# BB-cape.net
KiCad netlist of a schematic drawn in EAGLE
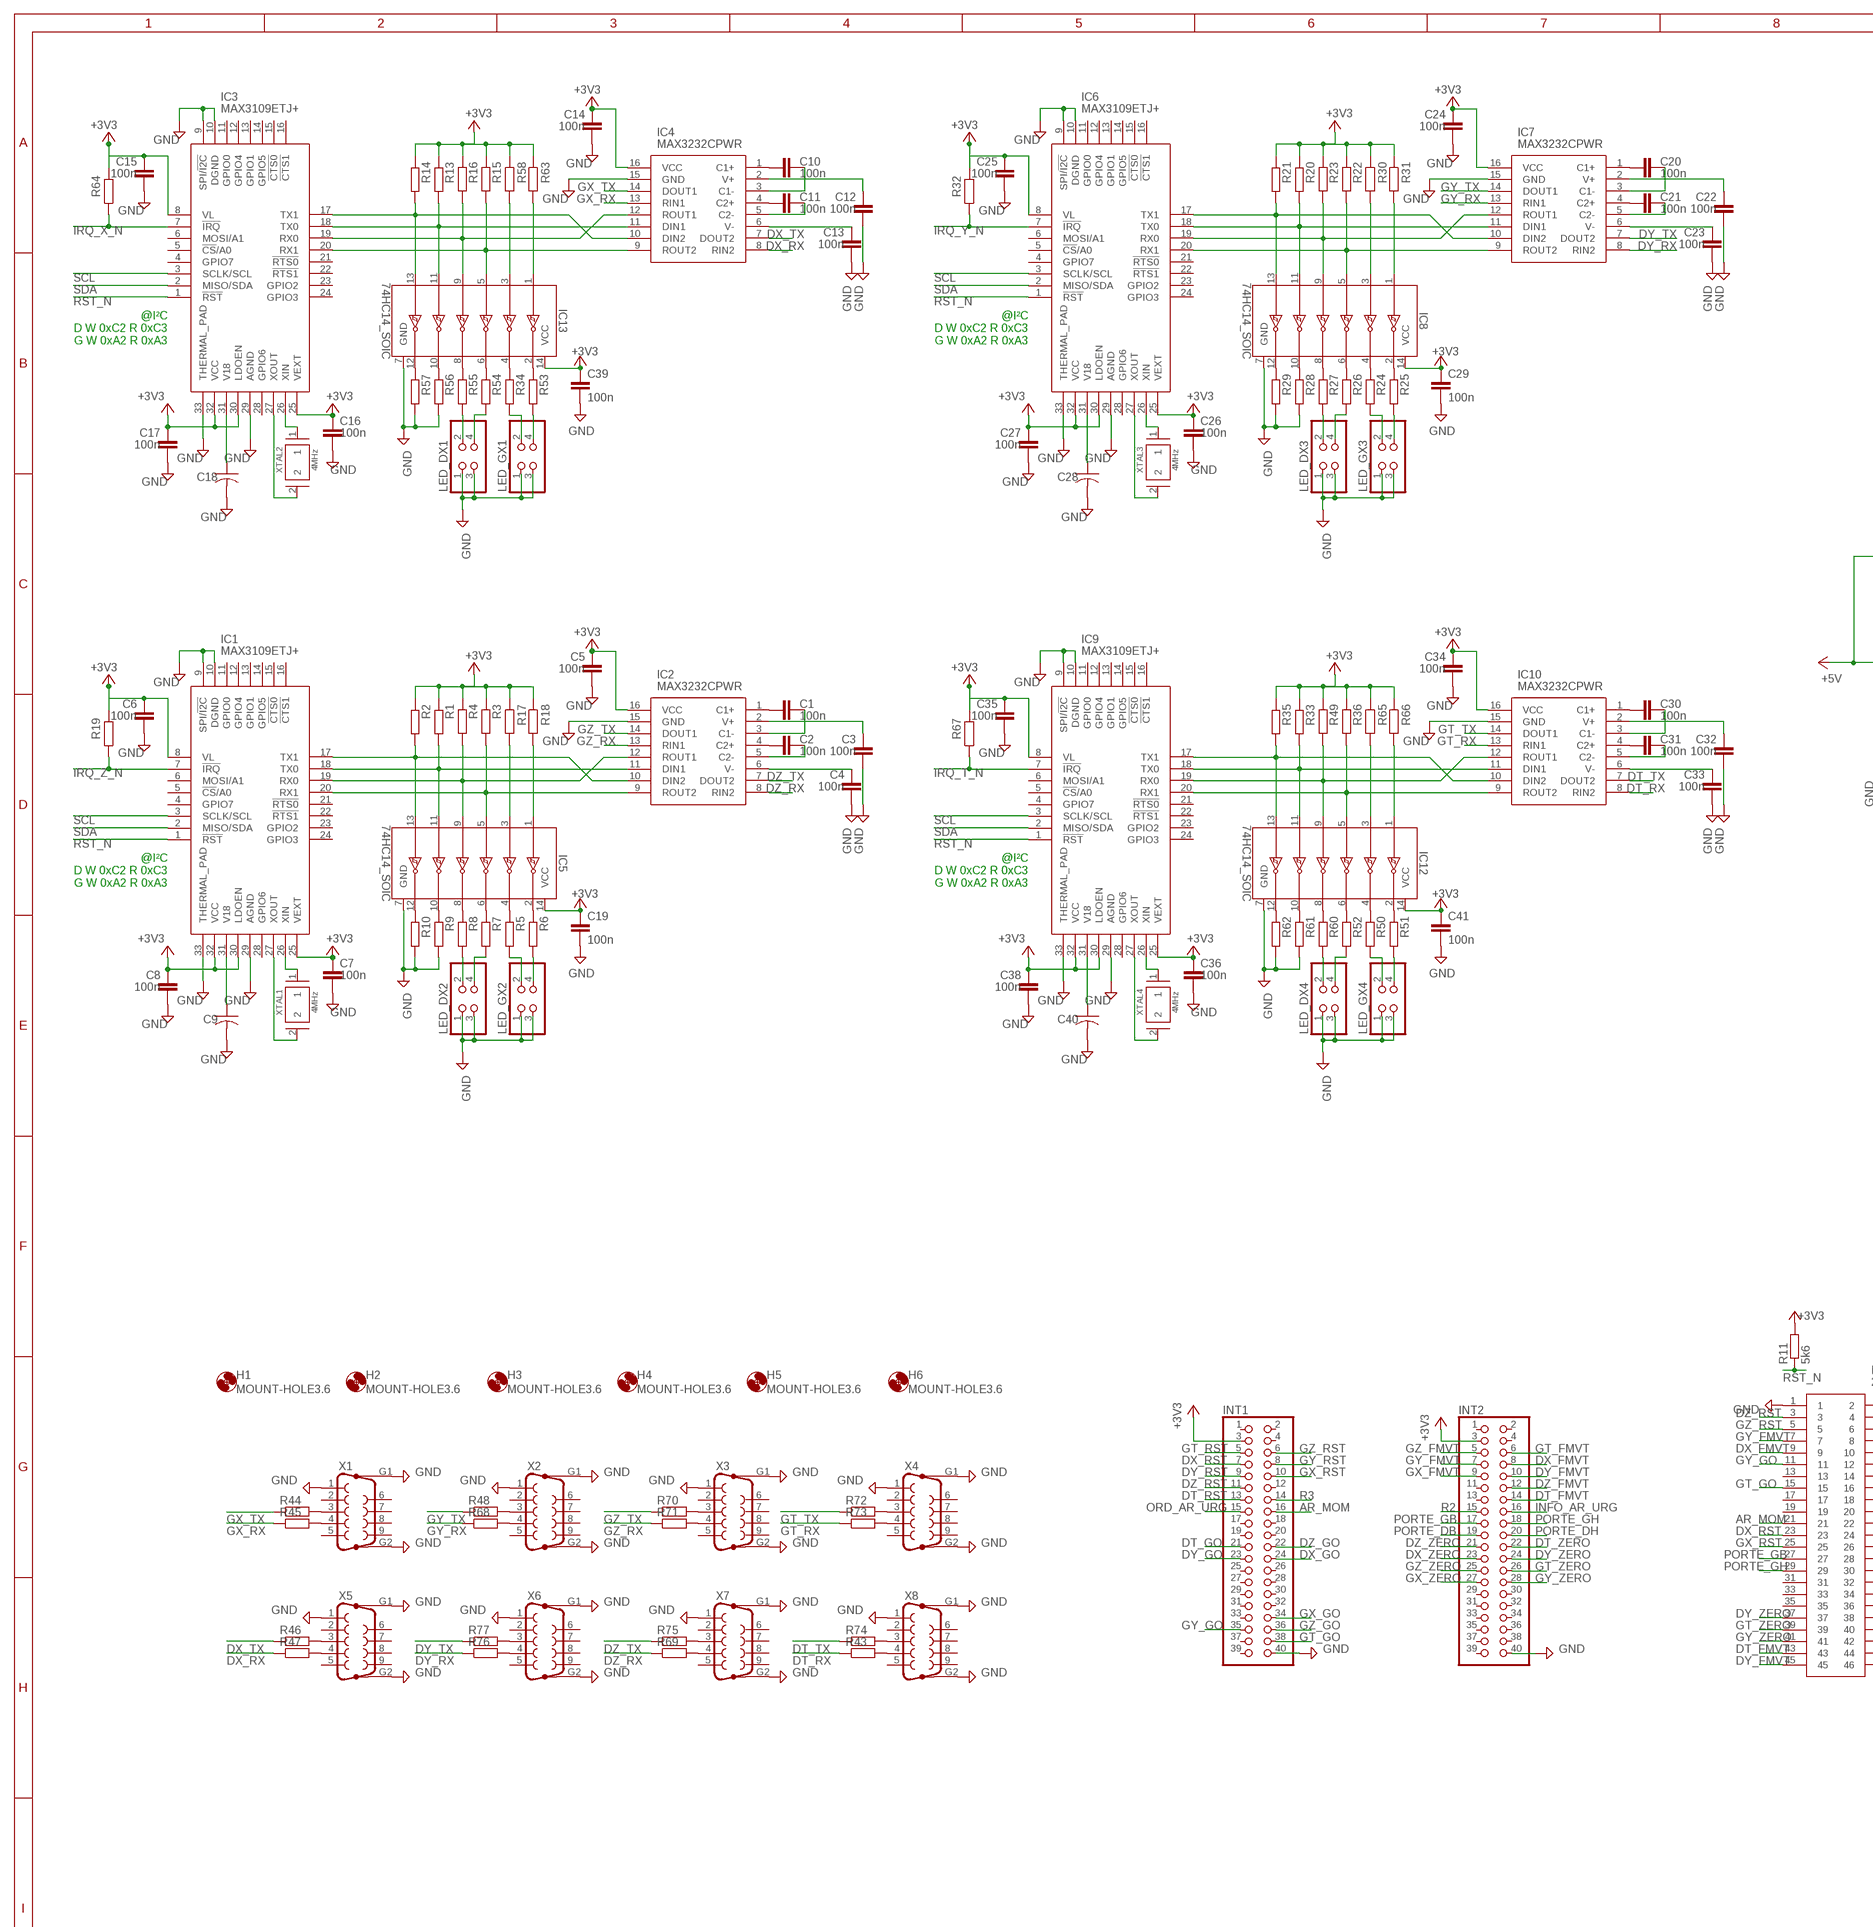
[diagram p0: schematic, sheet 1, part 1 of 2]
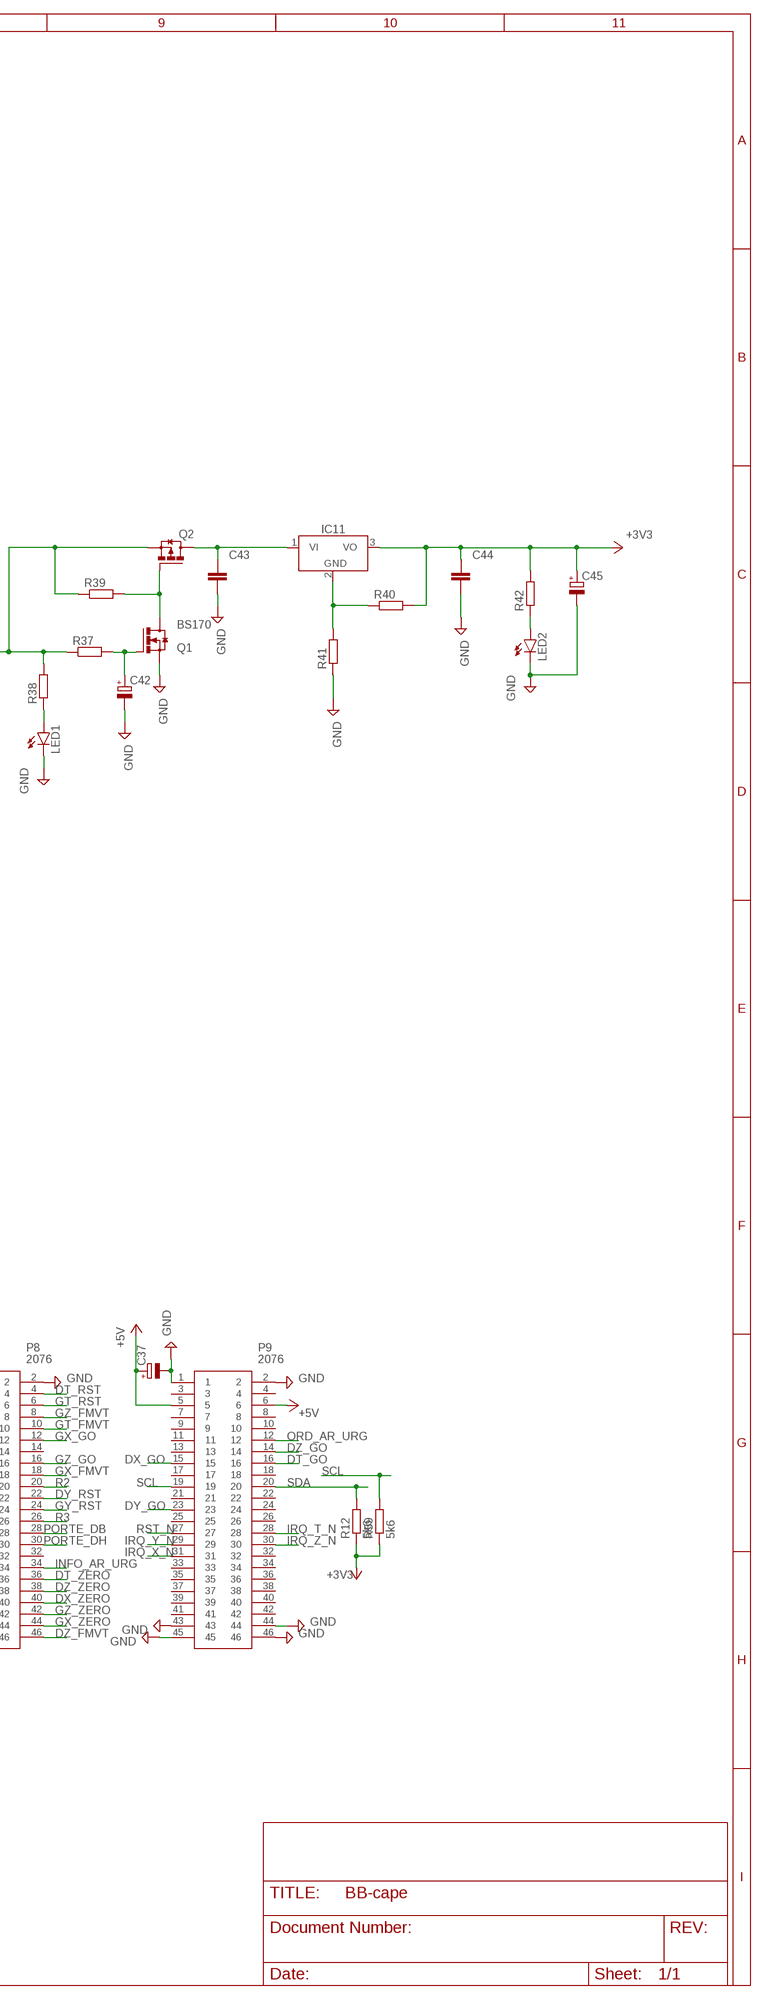
[diagram p1: schematic, sheet 1, part 2 of 2]

(export (version "E")
  (design (tool "Eeschema 10.0.6"))
  (components
    (comp (ref "C1")
      (value "100n")
      (footprint "eagle-import:C0603")
      (libsource (lib "eagle-import") (part "C-EUC0603"))
    )
    (comp (ref "C2")
      (value "100n")
      (footprint "eagle-import:C0603")
      (libsource (lib "eagle-import") (part "C-EUC0603"))
    )
    (comp (ref "C3")
      (value "100n")
      (footprint "eagle-import:C0603")
      (libsource (lib "eagle-import") (part "C-EUC0603"))
    )
    (comp (ref "C4")
      (value "100n")
      (footprint "eagle-import:C0603")
      (libsource (lib "eagle-import") (part "C-EUC0603"))
    )
    (comp (ref "C5")
      (value "100n")
      (footprint "eagle-import:C0603")
      (libsource (lib "eagle-import") (part "C-EUC0603"))
    )
    (comp (ref "C6")
      (value "100n")
      (footprint "eagle-import:C0603")
      (libsource (lib "eagle-import") (part "C-EUC0603"))
    )
    (comp (ref "C7")
      (value "100n")
      (footprint "eagle-import:C0603")
      (libsource (lib "eagle-import") (part "C-EUC0603"))
    )
    (comp (ref "C8")
      (value "100n")
      (footprint "eagle-import:C0603")
      (libsource (lib "eagle-import") (part "C-EUC0603"))
    )
    (comp (ref "C9")
      (value "C-USC1206")
      (footprint "eagle-import:C1206")
      (libsource (lib "eagle-import") (part "C-USC1206"))
    )
    (comp (ref "C10")
      (value "100n")
      (footprint "eagle-import:C0603")
      (libsource (lib "eagle-import") (part "C-EUC0603"))
    )
    (comp (ref "C11")
      (value "100n")
      (footprint "eagle-import:C0603")
      (libsource (lib "eagle-import") (part "C-EUC0603"))
    )
    (comp (ref "C12")
      (value "100n")
      (footprint "eagle-import:C0603")
      (libsource (lib "eagle-import") (part "C-EUC0603"))
    )
    (comp (ref "C13")
      (value "100n")
      (footprint "eagle-import:C0603")
      (libsource (lib "eagle-import") (part "C-EUC0603"))
    )
    (comp (ref "C14")
      (value "100n")
      (footprint "eagle-import:C0603")
      (libsource (lib "eagle-import") (part "C-EUC0603"))
    )
    (comp (ref "C15")
      (value "100n")
      (footprint "eagle-import:C0603")
      (libsource (lib "eagle-import") (part "C-EUC0603"))
    )
    (comp (ref "C16")
      (value "100n")
      (footprint "eagle-import:C0603")
      (libsource (lib "eagle-import") (part "C-EUC0603"))
    )
    (comp (ref "C17")
      (value "100n")
      (footprint "eagle-import:C0603")
      (libsource (lib "eagle-import") (part "C-EUC0603"))
    )
    (comp (ref "C18")
      (value "C-USC1206")
      (footprint "eagle-import:C1206")
      (libsource (lib "eagle-import") (part "C-USC1206"))
    )
    (comp (ref "C19")
      (value "100n")
      (footprint "eagle-import:C0603")
      (libsource (lib "eagle-import") (part "C-EUC0603"))
    )
    (comp (ref "C20")
      (value "100n")
      (footprint "eagle-import:C0603")
      (libsource (lib "eagle-import") (part "C-EUC0603"))
    )
    (comp (ref "C21")
      (value "100n")
      (footprint "eagle-import:C0603")
      (libsource (lib "eagle-import") (part "C-EUC0603"))
    )
    (comp (ref "C22")
      (value "100n")
      (footprint "eagle-import:C0603")
      (libsource (lib "eagle-import") (part "C-EUC0603"))
    )
    (comp (ref "C23")
      (value "100n")
      (footprint "eagle-import:C0603")
      (libsource (lib "eagle-import") (part "C-EUC0603"))
    )
    (comp (ref "C24")
      (value "100n")
      (footprint "eagle-import:C0603")
      (libsource (lib "eagle-import") (part "C-EUC0603"))
    )
    (comp (ref "C25")
      (value "100n")
      (footprint "eagle-import:C0603")
      (libsource (lib "eagle-import") (part "C-EUC0603"))
    )
    (comp (ref "C26")
      (value "100n")
      (footprint "eagle-import:C0603")
      (libsource (lib "eagle-import") (part "C-EUC0603"))
    )
    (comp (ref "C27")
      (value "100n")
      (footprint "eagle-import:C0603")
      (libsource (lib "eagle-import") (part "C-EUC0603"))
    )
    (comp (ref "C28")
      (value "C-USC1206")
      (footprint "eagle-import:C1206")
      (libsource (lib "eagle-import") (part "C-USC1206"))
    )
    (comp (ref "C29")
      (value "100n")
      (footprint "eagle-import:C0603")
      (libsource (lib "eagle-import") (part "C-EUC0603"))
    )
    (comp (ref "C30")
      (value "100n")
      (footprint "eagle-import:C0603")
      (libsource (lib "eagle-import") (part "C-EUC0603"))
    )
    (comp (ref "C31")
      (value "100n")
      (footprint "eagle-import:C0603")
      (libsource (lib "eagle-import") (part "C-EUC0603"))
    )
    (comp (ref "C32")
      (value "100n")
      (footprint "eagle-import:C0603")
      (libsource (lib "eagle-import") (part "C-EUC0603"))
    )
    (comp (ref "C33")
      (value "100n")
      (footprint "eagle-import:C0603")
      (libsource (lib "eagle-import") (part "C-EUC0603"))
    )
    (comp (ref "C34")
      (value "100n")
      (footprint "eagle-import:C0603")
      (libsource (lib "eagle-import") (part "C-EUC0603"))
    )
    (comp (ref "C35")
      (value "100n")
      (footprint "eagle-import:C0603")
      (libsource (lib "eagle-import") (part "C-EUC0603"))
    )
    (comp (ref "C36")
      (value "100n")
      (footprint "eagle-import:C0603")
      (libsource (lib "eagle-import") (part "C-EUC0603"))
    )
    (comp (ref "C37")
      (value "CPOL-EUE2.5-6")
      (footprint "eagle-import:E2,5-6")
      (libsource (lib "eagle-import") (part "CPOL-EUE2.5-6"))
    )
    (comp (ref "C38")
      (value "100n")
      (footprint "eagle-import:C0603")
      (libsource (lib "eagle-import") (part "C-EUC0603"))
    )
    (comp (ref "C39")
      (value "100n")
      (footprint "eagle-import:C0603")
      (libsource (lib "eagle-import") (part "C-EUC0603"))
    )
    (comp (ref "C40")
      (value "C-USC1206")
      (footprint "eagle-import:C1206")
      (libsource (lib "eagle-import") (part "C-USC1206"))
    )
    (comp (ref "C41")
      (value "100n")
      (footprint "eagle-import:C0603")
      (libsource (lib "eagle-import") (part "C-EUC0603"))
    )
    (comp (ref "C42")
      (value "CPOL-EUE2.5-6")
      (footprint "eagle-import:E2,5-6")
      (libsource (lib "eagle-import") (part "CPOL-EUE2.5-6"))
    )
    (comp (ref "C43")
      (value "C_CHIP-1210(3225-METRIC)")
      (footprint "eagle-import:CAPC3225X135")
      (libsource (lib "eagle-import") (part "CCHIP-1210(3225-METRIC)_"))
    )
    (comp (ref "C44")
      (value "C_CHIP-1210(3225-METRIC)")
      (footprint "eagle-import:CAPC3225X135")
      (libsource (lib "eagle-import") (part "CCHIP-1210(3225-METRIC)_"))
    )
    (comp (ref "C45")
      (value "CPOL-EUE2.5-6")
      (footprint "eagle-import:E2,5-6")
      (libsource (lib "eagle-import") (part "CPOL-EUE2.5-6"))
    )
    (comp (ref "H1")
      (value "MOUNT-HOLE3.6")
      (footprint "eagle-import:3,6")
      (libsource (lib "eagle-import") (part "MOUNT-HOLE3.6"))
    )
    (comp (ref "H2")
      (value "MOUNT-HOLE3.6")
      (footprint "eagle-import:3,6")
      (libsource (lib "eagle-import") (part "MOUNT-HOLE3.6"))
    )
    (comp (ref "H3")
      (value "MOUNT-HOLE3.6")
      (footprint "eagle-import:3,6")
      (libsource (lib "eagle-import") (part "MOUNT-HOLE3.6"))
    )
    (comp (ref "H4")
      (value "MOUNT-HOLE3.6")
      (footprint "eagle-import:3,6")
      (libsource (lib "eagle-import") (part "MOUNT-HOLE3.6"))
    )
    (comp (ref "H5")
      (value "MOUNT-HOLE3.6")
      (footprint "eagle-import:3,6")
      (libsource (lib "eagle-import") (part "MOUNT-HOLE3.6"))
    )
    (comp (ref "H6")
      (value "MOUNT-HOLE3.6")
      (footprint "eagle-import:3,6")
      (libsource (lib "eagle-import") (part "MOUNT-HOLE3.6"))
    )
    (comp (ref "IC1")
      (value "MAX3109ETJ+")
      (footprint "eagle-import:QFN50P500X500X80-33N")
      (fields (field (name "MOUSER_PART_NUMBER") "700-MAX3109ETJ+"))
      (libsource (lib "eagle-import") (part "MAX3109ETJ+"))
    )
    (comp (ref "IC2")
      (value "MAX3232CPWR")
      (footprint "eagle-import:SOP65P640X120-16N")
      (fields (field (name "MOUSER_PART_NUMBER") "595-MAX3232CPWR"))
      (libsource (lib "eagle-import") (part "MAX3232CPWR"))
    )
    (comp (ref "IC3")
      (value "MAX3109ETJ+")
      (footprint "eagle-import:QFN50P500X500X80-33N")
      (fields (field (name "MOUSER_PART_NUMBER") "700-MAX3109ETJ+"))
      (libsource (lib "eagle-import") (part "MAX3109ETJ+"))
    )
    (comp (ref "IC4")
      (value "MAX3232CPWR")
      (footprint "eagle-import:SOP65P640X120-16N")
      (fields (field (name "MOUSER_PART_NUMBER") "595-MAX3232CPWR"))
      (libsource (lib "eagle-import") (part "MAX3232CPWR"))
    )
    (comp (ref "IC5")
      (value "74HC14_SOIC")
      (footprint "eagle-import:SOIC127P600X175-14N")
      (fields (field (name "MANUFACTURER") "Generic"))
      (libsource (lib "eagle-import") (part "74HC14_SOIC"))
    )
    (comp (ref "IC6")
      (value "MAX3109ETJ+")
      (footprint "eagle-import:QFN50P500X500X80-33N")
      (fields (field (name "MOUSER_PART_NUMBER") "700-MAX3109ETJ+"))
      (libsource (lib "eagle-import") (part "MAX3109ETJ+"))
    )
    (comp (ref "IC7")
      (value "MAX3232CPWR")
      (footprint "eagle-import:SOP65P640X120-16N")
      (fields (field (name "MOUSER_PART_NUMBER") "595-MAX3232CPWR"))
      (libsource (lib "eagle-import") (part "MAX3232CPWR"))
    )
    (comp (ref "IC8")
      (value "74HC14_SOIC")
      (footprint "eagle-import:SOIC127P600X175-14N")
      (fields (field (name "MANUFACTURER") "Generic"))
      (libsource (lib "eagle-import") (part "74HC14_SOIC"))
    )
    (comp (ref "IC9")
      (value "MAX3109ETJ+")
      (footprint "eagle-import:QFN50P500X500X80-33N")
      (fields (field (name "MOUSER_PART_NUMBER") "700-MAX3109ETJ+"))
      (libsource (lib "eagle-import") (part "MAX3109ETJ+"))
    )
    (comp (ref "IC10")
      (value "MAX3232CPWR")
      (footprint "eagle-import:SOP65P640X120-16N")
      (fields (field (name "MOUSER_PART_NUMBER") "595-MAX3232CPWR"))
      (libsource (lib "eagle-import") (part "MAX3232CPWR"))
    )
    (comp (ref "IC11")
      (value "LM7805_TO220V")
      (footprint "eagle-import:TO220V")
      (fields (field (name "MANUFACTURER") "Generic"))
      (libsource (lib "eagle-import") (part "LM7805_TO220V"))
    )
    (comp (ref "IC12")
      (value "74HC14_SOIC")
      (footprint "eagle-import:SOIC127P600X175-14N")
      (fields (field (name "MANUFACTURER") "Generic"))
      (libsource (lib "eagle-import") (part "74HC14_SOIC"))
    )
    (comp (ref "IC13")
      (value "74HC14_SOIC")
      (footprint "eagle-import:SOIC127P600X175-14N")
      (fields (field (name "MANUFACTURER") "Generic"))
      (libsource (lib "eagle-import") (part "74HC14_SOIC"))
    )
    (comp (ref "INT1")
      (value "PINHD-2X20")
      (footprint "eagle-import:2X20")
      (libsource (lib "eagle-import") (part "PINHD-2X20"))
    )
    (comp (ref "INT2")
      (value "PINHD-2X20")
      (footprint "eagle-import:2X20")
      (libsource (lib "eagle-import") (part "PINHD-2X20"))
    )
    (comp (ref "LED1")
      (value "TLLY4400")
      (footprint "eagle-import:LED3MM")
      (fields (field (name "MF") "VISHAY SEMICONDUCTOR"))
      (libsource (lib "eagle-import") (part "TLLY4400"))
    )
    (comp (ref "LED2")
      (value "TLLY4400")
      (footprint "eagle-import:LED3MM")
      (fields (field (name "MF") "VISHAY SEMICONDUCTOR"))
      (libsource (lib "eagle-import") (part "TLLY4400"))
    )
    (comp (ref "LED_DX1")
      (value "PINHD-2X2")
      (footprint "eagle-import:2X02")
      (libsource (lib "eagle-import") (part "PINHD-2X2"))
    )
    (comp (ref "LED_DX2")
      (value "PINHD-2X2")
      (footprint "eagle-import:2X02")
      (libsource (lib "eagle-import") (part "PINHD-2X2"))
    )
    (comp (ref "LED_DX3")
      (value "PINHD-2X2")
      (footprint "eagle-import:2X02")
      (libsource (lib "eagle-import") (part "PINHD-2X2"))
    )
    (comp (ref "LED_DX4")
      (value "PINHD-2X2")
      (footprint "eagle-import:2X02")
      (libsource (lib "eagle-import") (part "PINHD-2X2"))
    )
    (comp (ref "LED_GX1")
      (value "PINHD-2X2")
      (footprint "eagle-import:2X02")
      (libsource (lib "eagle-import") (part "PINHD-2X2"))
    )
    (comp (ref "LED_GX2")
      (value "PINHD-2X2")
      (footprint "eagle-import:2X02")
      (libsource (lib "eagle-import") (part "PINHD-2X2"))
    )
    (comp (ref "LED_GX3")
      (value "PINHD-2X2")
      (footprint "eagle-import:2X02")
      (libsource (lib "eagle-import") (part "PINHD-2X2"))
    )
    (comp (ref "LED_GX4")
      (value "PINHD-2X2")
      (footprint "eagle-import:2X02")
      (libsource (lib "eagle-import") (part "PINHD-2X2"))
    )
    (comp (ref "P8")
      (value "2076")
      (footprint "eagle-import:HDRV46W64P254_2X23_5842X500X87")
      (fields (field (name "MOUSER_PART_NUMBER") "485-2076"))
      (libsource (lib "eagle-import") (part "2076"))
    )
    (comp (ref "P9")
      (value "2076")
      (footprint "eagle-import:HDRV46W64P254_2X23_5842X500X87")
      (fields (field (name "MOUSER_PART_NUMBER") "485-2076"))
      (libsource (lib "eagle-import") (part "2076"))
    )
    (comp (ref "Q1")
      (value "BS170")
      (footprint "eagle-import:TO92-3")
      (fields
        (field (name "DIGIKEY_PART_NUMBER") "2156-BS170-ND")
        (field (name "MANUFACTURER") "Fairchild Semiconductor")
        (field (name "CREATED_BY") "PCBLayout.com")
      )
      (libsource (lib "eagle-import") (part "BS170"))
    )
    (comp (ref "Q2")
      (value "IRF9540PBF")
      (footprint "eagle-import:TO-220")
      (fields
        (field (name "DIGIKEY_PART_NUMBER") "IRF9540PBF-ND")
        (field (name "MANUFACTURER") "Vishay Siliconix")
        (field (name "CREATED_BY") "PCBLayout.com")
      )
      (libsource (lib "eagle-import") (part "IRF9540PBF"))
    )
    (comp (ref "R1")
      (value "R-EU_R0603")
      (footprint "eagle-import:R0603")
      (libsource (lib "eagle-import") (part "R-EU_R0603"))
    )
    (comp (ref "R2")
      (value "R-EU_R0603")
      (footprint "eagle-import:R0603")
      (libsource (lib "eagle-import") (part "R-EU_R0603"))
    )
    (comp (ref "R3")
      (value "R-EU_R0603")
      (footprint "eagle-import:R0603")
      (libsource (lib "eagle-import") (part "R-EU_R0603"))
    )
    (comp (ref "R4")
      (value "R-EU_R0603")
      (footprint "eagle-import:R0603")
      (libsource (lib "eagle-import") (part "R-EU_R0603"))
    )
    (comp (ref "R5")
      (value "R-EU_R0603")
      (footprint "eagle-import:R0603")
      (libsource (lib "eagle-import") (part "R-EU_R0603"))
    )
    (comp (ref "R6")
      (value "R-EU_R0603")
      (footprint "eagle-import:R0603")
      (libsource (lib "eagle-import") (part "R-EU_R0603"))
    )
    (comp (ref "R7")
      (value "R-EU_R0603")
      (footprint "eagle-import:R0603")
      (libsource (lib "eagle-import") (part "R-EU_R0603"))
    )
    (comp (ref "R8")
      (value "R-EU_R0603")
      (footprint "eagle-import:R0603")
      (libsource (lib "eagle-import") (part "R-EU_R0603"))
    )
    (comp (ref "R9")
      (value "R-EU_R0603")
      (footprint "eagle-import:R0603")
      (libsource (lib "eagle-import") (part "R-EU_R0603"))
    )
    (comp (ref "R10")
      (value "R-EU_R0603")
      (footprint "eagle-import:R0603")
      (libsource (lib "eagle-import") (part "R-EU_R0603"))
    )
    (comp (ref "R11")
      (value "5k6")
      (footprint "eagle-import:R0603")
      (libsource (lib "eagle-import") (part "R-EU_R0603"))
    )
    (comp (ref "R12")
      (value "5k6")
      (footprint "eagle-import:R0603")
      (libsource (lib "eagle-import") (part "R-EU_R0603"))
    )
    (comp (ref "R13")
      (value "R-EU_R0603")
      (footprint "eagle-import:R0603")
      (libsource (lib "eagle-import") (part "R-EU_R0603"))
    )
    (comp (ref "R14")
      (value "R-EU_R0603")
      (footprint "eagle-import:R0603")
      (libsource (lib "eagle-import") (part "R-EU_R0603"))
    )
    (comp (ref "R15")
      (value "R-EU_R0603")
      (footprint "eagle-import:R0603")
      (libsource (lib "eagle-import") (part "R-EU_R0603"))
    )
    (comp (ref "R16")
      (value "R-EU_R0603")
      (footprint "eagle-import:R0603")
      (libsource (lib "eagle-import") (part "R-EU_R0603"))
    )
    (comp (ref "R17")
      (value "R-EU_R0603")
      (footprint "eagle-import:R0603")
      (libsource (lib "eagle-import") (part "R-EU_R0603"))
    )
    (comp (ref "R18")
      (value "R-EU_R0603")
      (footprint "eagle-import:R0603")
      (libsource (lib "eagle-import") (part "R-EU_R0603"))
    )
    (comp (ref "R19")
      (value "R-EU_R0603")
      (footprint "eagle-import:R0603")
      (libsource (lib "eagle-import") (part "R-EU_R0603"))
    )
    (comp (ref "R20")
      (value "R-EU_R0603")
      (footprint "eagle-import:R0603")
      (libsource (lib "eagle-import") (part "R-EU_R0603"))
    )
    (comp (ref "R21")
      (value "R-EU_R0603")
      (footprint "eagle-import:R0603")
      (libsource (lib "eagle-import") (part "R-EU_R0603"))
    )
    (comp (ref "R22")
      (value "R-EU_R0603")
      (footprint "eagle-import:R0603")
      (libsource (lib "eagle-import") (part "R-EU_R0603"))
    )
    (comp (ref "R23")
      (value "R-EU_R0603")
      (footprint "eagle-import:R0603")
      (libsource (lib "eagle-import") (part "R-EU_R0603"))
    )
    (comp (ref "R24")
      (value "R-EU_R0603")
      (footprint "eagle-import:R0603")
      (libsource (lib "eagle-import") (part "R-EU_R0603"))
    )
    (comp (ref "R25")
      (value "R-EU_R0603")
      (footprint "eagle-import:R0603")
      (libsource (lib "eagle-import") (part "R-EU_R0603"))
    )
    (comp (ref "R26")
      (value "R-EU_R0603")
      (footprint "eagle-import:R0603")
      (libsource (lib "eagle-import") (part "R-EU_R0603"))
    )
    (comp (ref "R27")
      (value "R-EU_R0603")
      (footprint "eagle-import:R0603")
      (libsource (lib "eagle-import") (part "R-EU_R0603"))
    )
    (comp (ref "R28")
      (value "R-EU_R0603")
      (footprint "eagle-import:R0603")
      (libsource (lib "eagle-import") (part "R-EU_R0603"))
    )
    (comp (ref "R29")
      (value "R-EU_R0603")
      (footprint "eagle-import:R0603")
      (libsource (lib "eagle-import") (part "R-EU_R0603"))
    )
    (comp (ref "R30")
      (value "R-EU_R0603")
      (footprint "eagle-import:R0603")
      (libsource (lib "eagle-import") (part "R-EU_R0603"))
    )
    (comp (ref "R31")
      (value "R-EU_R0603")
      (footprint "eagle-import:R0603")
      (libsource (lib "eagle-import") (part "R-EU_R0603"))
    )
    (comp (ref "R32")
      (value "R-EU_R0603")
      (footprint "eagle-import:R0603")
      (libsource (lib "eagle-import") (part "R-EU_R0603"))
    )
    (comp (ref "R33")
      (value "R-EU_R0603")
      (footprint "eagle-import:R0603")
      (libsource (lib "eagle-import") (part "R-EU_R0603"))
    )
    (comp (ref "R34")
      (value "R-EU_R0603")
      (footprint "eagle-import:R0603")
      (libsource (lib "eagle-import") (part "R-EU_R0603"))
    )
    (comp (ref "R35")
      (value "R-EU_R0603")
      (footprint "eagle-import:R0603")
      (libsource (lib "eagle-import") (part "R-EU_R0603"))
    )
    (comp (ref "R36")
      (value "R-EU_R0603")
      (footprint "eagle-import:R0603")
      (libsource (lib "eagle-import") (part "R-EU_R0603"))
    )
    (comp (ref "R37")
      (value "R-EU_R0603")
      (footprint "eagle-import:R0603")
      (libsource (lib "eagle-import") (part "R-EU_R0603"))
    )
    (comp (ref "R38")
      (value "R-EU_R0603")
      (footprint "eagle-import:R0603")
      (libsource (lib "eagle-import") (part "R-EU_R0603"))
    )
    (comp (ref "R39")
      (value "R-EU_R0603")
      (footprint "eagle-import:R0603")
      (libsource (lib "eagle-import") (part "R-EU_R0603"))
    )
    (comp (ref "R40")
      (value "R-EU_R0603")
      (footprint "eagle-import:R0603")
      (libsource (lib "eagle-import") (part "R-EU_R0603"))
    )
    (comp (ref "R41")
      (value "R-EU_R0603")
      (footprint "eagle-import:R0603")
      (libsource (lib "eagle-import") (part "R-EU_R0603"))
    )
    (comp (ref "R42")
      (value "R-EU_R0603")
      (footprint "eagle-import:R0603")
      (libsource (lib "eagle-import") (part "R-EU_R0603"))
    )
    (comp (ref "R43")
      (value "R-EU_R0603")
      (footprint "eagle-import:R0603")
      (libsource (lib "eagle-import") (part "R-EU_R0603"))
    )
    (comp (ref "R44")
      (value "R-EU_R0603")
      (footprint "eagle-import:R0603")
      (libsource (lib "eagle-import") (part "R-EU_R0603"))
    )
    (comp (ref "R45")
      (value "R-EU_R0603")
      (footprint "eagle-import:R0603")
      (libsource (lib "eagle-import") (part "R-EU_R0603"))
    )
    (comp (ref "R46")
      (value "R-EU_R0603")
      (footprint "eagle-import:R0603")
      (libsource (lib "eagle-import") (part "R-EU_R0603"))
    )
    (comp (ref "R47")
      (value "R-EU_R0603")
      (footprint "eagle-import:R0603")
      (libsource (lib "eagle-import") (part "R-EU_R0603"))
    )
    (comp (ref "R48")
      (value "R-EU_R0603")
      (footprint "eagle-import:R0603")
      (libsource (lib "eagle-import") (part "R-EU_R0603"))
    )
    (comp (ref "R49")
      (value "R-EU_R0603")
      (footprint "eagle-import:R0603")
      (libsource (lib "eagle-import") (part "R-EU_R0603"))
    )
    (comp (ref "R50")
      (value "R-EU_R0603")
      (footprint "eagle-import:R0603")
      (libsource (lib "eagle-import") (part "R-EU_R0603"))
    )
    (comp (ref "R51")
      (value "R-EU_R0603")
      (footprint "eagle-import:R0603")
      (libsource (lib "eagle-import") (part "R-EU_R0603"))
    )
    (comp (ref "R52")
      (value "R-EU_R0603")
      (footprint "eagle-import:R0603")
      (libsource (lib "eagle-import") (part "R-EU_R0603"))
    )
    (comp (ref "R53")
      (value "R-EU_R0603")
      (footprint "eagle-import:R0603")
      (libsource (lib "eagle-import") (part "R-EU_R0603"))
    )
    (comp (ref "R54")
      (value "R-EU_R0603")
      (footprint "eagle-import:R0603")
      (libsource (lib "eagle-import") (part "R-EU_R0603"))
    )
    (comp (ref "R55")
      (value "R-EU_R0603")
      (footprint "eagle-import:R0603")
      (libsource (lib "eagle-import") (part "R-EU_R0603"))
    )
    (comp (ref "R56")
      (value "R-EU_R0603")
      (footprint "eagle-import:R0603")
      (libsource (lib "eagle-import") (part "R-EU_R0603"))
    )
    (comp (ref "R57")
      (value "R-EU_R0603")
      (footprint "eagle-import:R0603")
      (libsource (lib "eagle-import") (part "R-EU_R0603"))
    )
    (comp (ref "R58")
      (value "R-EU_R0603")
      (footprint "eagle-import:R0603")
      (libsource (lib "eagle-import") (part "R-EU_R0603"))
    )
    (comp (ref "R59")
      (value "5k6")
      (footprint "eagle-import:R0603")
      (libsource (lib "eagle-import") (part "R-EU_R0603"))
    )
    (comp (ref "R60")
      (value "R-EU_R0603")
      (footprint "eagle-import:R0603")
      (libsource (lib "eagle-import") (part "R-EU_R0603"))
    )
    (comp (ref "R61")
      (value "R-EU_R0603")
      (footprint "eagle-import:R0603")
      (libsource (lib "eagle-import") (part "R-EU_R0603"))
    )
    (comp (ref "R62")
      (value "R-EU_R0603")
      (footprint "eagle-import:R0603")
      (libsource (lib "eagle-import") (part "R-EU_R0603"))
    )
    (comp (ref "R63")
      (value "R-EU_R0603")
      (footprint "eagle-import:R0603")
      (libsource (lib "eagle-import") (part "R-EU_R0603"))
    )
    (comp (ref "R64")
      (value "R-EU_R0603")
      (footprint "eagle-import:R0603")
      (libsource (lib "eagle-import") (part "R-EU_R0603"))
    )
    (comp (ref "R65")
      (value "R-EU_R0603")
      (footprint "eagle-import:R0603")
      (libsource (lib "eagle-import") (part "R-EU_R0603"))
    )
    (comp (ref "R66")
      (value "R-EU_R0603")
      (footprint "eagle-import:R0603")
      (libsource (lib "eagle-import") (part "R-EU_R0603"))
    )
    (comp (ref "R67")
      (value "R-EU_R0603")
      (footprint "eagle-import:R0603")
      (libsource (lib "eagle-import") (part "R-EU_R0603"))
    )
    (comp (ref "R68")
      (value "R-EU_R0603")
      (footprint "eagle-import:R0603")
      (libsource (lib "eagle-import") (part "R-EU_R0603"))
    )
    (comp (ref "R69")
      (value "R-EU_R0603")
      (footprint "eagle-import:R0603")
      (libsource (lib "eagle-import") (part "R-EU_R0603"))
    )
    (comp (ref "R70")
      (value "R-EU_R0603")
      (footprint "eagle-import:R0603")
      (libsource (lib "eagle-import") (part "R-EU_R0603"))
    )
    (comp (ref "R71")
      (value "R-EU_R0603")
      (footprint "eagle-import:R0603")
      (libsource (lib "eagle-import") (part "R-EU_R0603"))
    )
    (comp (ref "R72")
      (value "R-EU_R0603")
      (footprint "eagle-import:R0603")
      (libsource (lib "eagle-import") (part "R-EU_R0603"))
    )
    (comp (ref "R73")
      (value "R-EU_R0603")
      (footprint "eagle-import:R0603")
      (libsource (lib "eagle-import") (part "R-EU_R0603"))
    )
    (comp (ref "R74")
      (value "R-EU_R0603")
      (footprint "eagle-import:R0603")
      (libsource (lib "eagle-import") (part "R-EU_R0603"))
    )
    (comp (ref "R75")
      (value "R-EU_R0603")
      (footprint "eagle-import:R0603")
      (libsource (lib "eagle-import") (part "R-EU_R0603"))
    )
    (comp (ref "R76")
      (value "R-EU_R0603")
      (footprint "eagle-import:R0603")
      (libsource (lib "eagle-import") (part "R-EU_R0603"))
    )
    (comp (ref "R77")
      (value "R-EU_R0603")
      (footprint "eagle-import:R0603")
      (libsource (lib "eagle-import") (part "R-EU_R0603"))
    )
    (comp (ref "X1")
      (value "F09HP")
      (footprint "eagle-import:F09HP")
      (libsource (lib "eagle-import") (part "F09HP"))
    )
    (comp (ref "X2")
      (value "F09HP")
      (footprint "eagle-import:F09HP")
      (libsource (lib "eagle-import") (part "F09HP"))
    )
    (comp (ref "X3")
      (value "F09HP")
      (footprint "eagle-import:F09HP")
      (libsource (lib "eagle-import") (part "F09HP"))
    )
    (comp (ref "X4")
      (value "F09HP")
      (footprint "eagle-import:F09HP")
      (libsource (lib "eagle-import") (part "F09HP"))
    )
    (comp (ref "X5")
      (value "F09HP")
      (footprint "eagle-import:F09HP")
      (libsource (lib "eagle-import") (part "F09HP"))
    )
    (comp (ref "X6")
      (value "F09HP")
      (footprint "eagle-import:F09HP")
      (libsource (lib "eagle-import") (part "F09HP"))
    )
    (comp (ref "X7")
      (value "F09HP")
      (footprint "eagle-import:F09HP")
      (libsource (lib "eagle-import") (part "F09HP"))
    )
    (comp (ref "X8")
      (value "F09HP")
      (footprint "eagle-import:F09HP")
      (libsource (lib "eagle-import") (part "F09HP"))
    )
    (comp (ref "XTAL1")
      (value "4MHz")
      (footprint "eagle-import:XTAL1147X477X420N")
      (fields
        (field (name "MANUFACTURER") "ABRACON")
        (field (name "MPN") "ABLS-16.000MHZ-S-R500MD2XF")
        (field (name "TOLERANCE") "20PPM")
      )
      (libsource (lib "eagle-import") (part "ABLS"))
    )
    (comp (ref "XTAL2")
      (value "4MHz")
      (footprint "eagle-import:XTAL1147X477X420N")
      (fields
        (field (name "MANUFACTURER") "ABRACON")
        (field (name "MPN") "ABLS-16.000MHZ-S-R500MD2XF")
        (field (name "TOLERANCE") "20PPM")
      )
      (libsource (lib "eagle-import") (part "ABLS"))
    )
    (comp (ref "XTAL3")
      (value "4MHz")
      (footprint "eagle-import:XTAL1147X477X420N")
      (fields
        (field (name "MANUFACTURER") "ABRACON")
        (field (name "MPN") "ABLS-16.000MHZ-S-R500MD2XF")
        (field (name "TOLERANCE") "20PPM")
      )
      (libsource (lib "eagle-import") (part "ABLS"))
    )
    (comp (ref "XTAL4")
      (value "4MHz")
      (footprint "eagle-import:XTAL1147X477X420N")
      (fields
        (field (name "MANUFACTURER") "ABRACON")
        (field (name "MPN") "ABLS-16.000MHZ-S-R500MD2XF")
        (field (name "TOLERANCE") "20PPM")
      )
      (libsource (lib "eagle-import") (part "ABLS"))
    )
  )
  (nets
    (net (code "1") (name "+3V3") (class "Default")
      (node (ref "C14") (pin "1") (pinfunction "1_1") (pintype "passive"))
      (node (ref "C15") (pin "1") (pinfunction "1_1") (pintype "passive"))
      (node (ref "C16") (pin "2") (pinfunction "2_2") (pintype "passive"))
      (node (ref "C17") (pin "2") (pinfunction "2_2") (pintype "passive"))
      (node (ref "C19") (pin "2") (pinfunction "2_2") (pintype "passive"))
      (node (ref "C24") (pin "1") (pinfunction "1_1") (pintype "passive"))
      (node (ref "C25") (pin "1") (pinfunction "1_1") (pintype "passive"))
      (node (ref "C26") (pin "2") (pinfunction "2_2") (pintype "passive"))
      (node (ref "C27") (pin "2") (pinfunction "2_2") (pintype "passive"))
      (node (ref "C29") (pin "2") (pinfunction "2_2") (pintype "passive"))
      (node (ref "C34") (pin "1") (pinfunction "1_1") (pintype "passive"))
      (node (ref "C35") (pin "1") (pinfunction "1_1") (pintype "passive"))
      (node (ref "C36") (pin "2") (pinfunction "2_2") (pintype "passive"))
      (node (ref "C38") (pin "2") (pinfunction "2_2") (pintype "passive"))
      (node (ref "C39") (pin "2") (pinfunction "2_2") (pintype "passive"))
      (node (ref "C41") (pin "2") (pinfunction "2_2") (pintype "passive"))
      (node (ref "C44") (pin "1") (pinfunction "1_1") (pintype "passive"))
      (node (ref "C45") (pin "+") (pinfunction "+_+") (pintype "passive"))
      (node (ref "C5") (pin "1") (pinfunction "1_1") (pintype "passive"))
      (node (ref "C6") (pin "1") (pinfunction "1_1") (pintype "passive"))
      (node (ref "C7") (pin "2") (pinfunction "2_2") (pintype "passive"))
      (node (ref "C8") (pin "2") (pinfunction "2_2") (pintype "passive"))
      (node (ref "IC1") (pin "25") (pinfunction "VEXT_25") (pintype "bidirectional"))
      (node (ref "IC1") (pin "30") (pinfunction "LDOEN_30") (pintype "bidirectional"))
      (node (ref "IC1") (pin "32") (pinfunction "VCC_32") (pintype "bidirectional"))
      (node (ref "IC1") (pin "8") (pinfunction "VL_8") (pintype "bidirectional"))
      (node (ref "IC10") (pin "16") (pinfunction "VCC_16") (pintype "bidirectional"))
      (node (ref "IC11") (pin "3") (pinfunction "VO_3") (pintype "output"))
      (node (ref "IC12") (pin "14") (pinfunction "VCC_14") (pintype "bidirectional"))
      (node (ref "IC13") (pin "14") (pinfunction "VCC_14") (pintype "bidirectional"))
      (node (ref "IC2") (pin "16") (pinfunction "VCC_16") (pintype "bidirectional"))
      (node (ref "IC3") (pin "25") (pinfunction "VEXT_25") (pintype "bidirectional"))
      (node (ref "IC3") (pin "30") (pinfunction "LDOEN_30") (pintype "bidirectional"))
      (node (ref "IC3") (pin "32") (pinfunction "VCC_32") (pintype "bidirectional"))
      (node (ref "IC3") (pin "8") (pinfunction "VL_8") (pintype "bidirectional"))
      (node (ref "IC4") (pin "16") (pinfunction "VCC_16") (pintype "bidirectional"))
      (node (ref "IC5") (pin "14") (pinfunction "VCC_14") (pintype "bidirectional"))
      (node (ref "IC6") (pin "25") (pinfunction "VEXT_25") (pintype "bidirectional"))
      (node (ref "IC6") (pin "30") (pinfunction "LDOEN_30") (pintype "bidirectional"))
      (node (ref "IC6") (pin "32") (pinfunction "VCC_32") (pintype "bidirectional"))
      (node (ref "IC6") (pin "8") (pinfunction "VL_8") (pintype "bidirectional"))
      (node (ref "IC7") (pin "16") (pinfunction "VCC_16") (pintype "bidirectional"))
      (node (ref "IC8") (pin "14") (pinfunction "VCC_14") (pintype "bidirectional"))
      (node (ref "IC9") (pin "25") (pinfunction "VEXT_25") (pintype "bidirectional"))
      (node (ref "IC9") (pin "30") (pinfunction "LDOEN_30") (pintype "bidirectional"))
      (node (ref "IC9") (pin "32") (pinfunction "VCC_32") (pintype "bidirectional"))
      (node (ref "IC9") (pin "8") (pinfunction "VL_8") (pintype "bidirectional"))
      (node (ref "INT1") (pin "3") (pinfunction "3_3") (pintype "passive"))
      (node (ref "INT2") (pin "3") (pinfunction "3_3") (pintype "passive"))
      (node (ref "R1") (pin "1") (pinfunction "1_1") (pintype "passive"))
      (node (ref "R11") (pin "2") (pinfunction "2_2") (pintype "passive"))
      (node (ref "R12") (pin "1") (pinfunction "1_1") (pintype "passive"))
      (node (ref "R13") (pin "1") (pinfunction "1_1") (pintype "passive"))
      (node (ref "R14") (pin "1") (pinfunction "1_1") (pintype "passive"))
      (node (ref "R15") (pin "2") (pinfunction "2_2") (pintype "passive"))
      (node (ref "R16") (pin "2") (pinfunction "2_2") (pintype "passive"))
      (node (ref "R17") (pin "1") (pinfunction "1_1") (pintype "passive"))
      (node (ref "R18") (pin "1") (pinfunction "1_1") (pintype "passive"))
      (node (ref "R19") (pin "2") (pinfunction "2_2") (pintype "passive"))
      (node (ref "R2") (pin "1") (pinfunction "1_1") (pintype "passive"))
      (node (ref "R20") (pin "1") (pinfunction "1_1") (pintype "passive"))
      (node (ref "R21") (pin "1") (pinfunction "1_1") (pintype "passive"))
      (node (ref "R22") (pin "2") (pinfunction "2_2") (pintype "passive"))
      (node (ref "R23") (pin "2") (pinfunction "2_2") (pintype "passive"))
      (node (ref "R3") (pin "2") (pinfunction "2_2") (pintype "passive"))
      (node (ref "R30") (pin "1") (pinfunction "1_1") (pintype "passive"))
      (node (ref "R31") (pin "1") (pinfunction "1_1") (pintype "passive"))
      (node (ref "R32") (pin "2") (pinfunction "2_2") (pintype "passive"))
      (node (ref "R33") (pin "1") (pinfunction "1_1") (pintype "passive"))
      (node (ref "R35") (pin "1") (pinfunction "1_1") (pintype "passive"))
      (node (ref "R36") (pin "2") (pinfunction "2_2") (pintype "passive"))
      (node (ref "R4") (pin "2") (pinfunction "2_2") (pintype "passive"))
      (node (ref "R40") (pin "2") (pinfunction "2_2") (pintype "passive"))
      (node (ref "R42") (pin "2") (pinfunction "2_2") (pintype "passive"))
      (node (ref "R49") (pin "2") (pinfunction "2_2") (pintype "passive"))
      (node (ref "R58") (pin "1") (pinfunction "1_1") (pintype "passive"))
      (node (ref "R59") (pin "1") (pinfunction "1_1") (pintype "passive"))
      (node (ref "R63") (pin "1") (pinfunction "1_1") (pintype "passive"))
      (node (ref "R64") (pin "2") (pinfunction "2_2") (pintype "passive"))
      (node (ref "R65") (pin "1") (pinfunction "1_1") (pintype "passive"))
      (node (ref "R66") (pin "1") (pinfunction "1_1") (pintype "passive"))
      (node (ref "R67") (pin "2") (pinfunction "2_2") (pintype "passive"))
    )
    (net (code "2") (name "+5V") (class "Default")
      (node (ref "C37") (pin "+") (pinfunction "+_+") (pintype "passive"))
      (node (ref "P9") (pin "5") (pinfunction "5_5") (pintype "bidirectional"))
      (node (ref "P9") (pin "6") (pinfunction "6_6") (pintype "bidirectional"))
      (node (ref "Q2") (pin "S") (pinfunction "S_S") (pintype "passive"))
      (node (ref "R37") (pin "1") (pinfunction "1_1") (pintype "passive"))
      (node (ref "R38") (pin "2") (pinfunction "2_2") (pintype "passive"))
      (node (ref "R39") (pin "1") (pinfunction "1_1") (pintype "passive"))
    )
    (net (code "3") (name "/AR_MOM") (class "Default")
      (node (ref "INT1") (pin "16") (pinfunction "16_16") (pintype "passive"))
      (node (ref "P8") (pin "21") (pinfunction "21_21") (pintype "bidirectional"))
    )
    (net (code "4") (name "/DT_FMVT") (class "Default")
      (node (ref "INT2") (pin "14") (pinfunction "14_14") (pintype "passive"))
      (node (ref "P8") (pin "43") (pinfunction "43_43") (pintype "bidirectional"))
    )
    (net (code "5") (name "/DT_GO") (class "Default")
      (node (ref "INT1") (pin "21") (pinfunction "21_21") (pintype "passive"))
      (node (ref "P9") (pin "16") (pinfunction "16_16") (pintype "bidirectional"))
    )
    (net (code "6") (name "/DT_RST") (class "Default")
      (node (ref "INT1") (pin "13") (pinfunction "13_13") (pintype "passive"))
      (node (ref "P8") (pin "4") (pinfunction "4_4") (pintype "bidirectional"))
    )
    (net (code "7") (name "/DT_RX") (class "Default")
      (node (ref "IC10") (pin "8") (pinfunction "RIN2_8") (pintype "bidirectional"))
      (node (ref "R43") (pin "1") (pinfunction "1_1") (pintype "passive"))
    )
    (net (code "8") (name "/DT_TX") (class "Default")
      (node (ref "IC10") (pin "7") (pinfunction "DOUT2_7") (pintype "bidirectional"))
      (node (ref "R74") (pin "1") (pinfunction "1_1") (pintype "passive"))
    )
    (net (code "9") (name "/DT_ZERO") (class "Default")
      (node (ref "INT2") (pin "22") (pinfunction "22_22") (pintype "passive"))
      (node (ref "P8") (pin "36") (pinfunction "36_36") (pintype "bidirectional"))
    )
    (net (code "10") (name "/DX_FMVT") (class "Default")
      (node (ref "INT2") (pin "8") (pinfunction "8_8") (pintype "passive"))
      (node (ref "P8") (pin "9") (pinfunction "9_9") (pintype "bidirectional"))
    )
    (net (code "11") (name "/DX_GO") (class "Default")
      (node (ref "INT1") (pin "24") (pinfunction "24_24") (pintype "passive"))
      (node (ref "P9") (pin "15") (pinfunction "15_15") (pintype "bidirectional"))
    )
    (net (code "12") (name "/DX_RST") (class "Default")
      (node (ref "INT1") (pin "7") (pinfunction "7_7") (pintype "passive"))
      (node (ref "P8") (pin "23") (pinfunction "23_23") (pintype "bidirectional"))
    )
    (net (code "13") (name "/DX_RX") (class "Default")
      (node (ref "IC4") (pin "8") (pinfunction "RIN2_8") (pintype "bidirectional"))
      (node (ref "R47") (pin "1") (pinfunction "1_1") (pintype "passive"))
    )
    (net (code "14") (name "/DX_TX") (class "Default")
      (node (ref "IC4") (pin "7") (pinfunction "DOUT2_7") (pintype "bidirectional"))
      (node (ref "R46") (pin "1") (pinfunction "1_1") (pintype "passive"))
    )
    (net (code "15") (name "/DX_ZERO") (class "Default")
      (node (ref "INT2") (pin "23") (pinfunction "23_23") (pintype "passive"))
      (node (ref "P8") (pin "40") (pinfunction "40_40") (pintype "bidirectional"))
    )
    (net (code "16") (name "/DY_FMVT") (class "Default")
      (node (ref "INT2") (pin "10") (pinfunction "10_10") (pintype "passive"))
      (node (ref "P8") (pin "45") (pinfunction "45_45") (pintype "bidirectional"))
    )
    (net (code "17") (name "/DY_GO") (class "Default")
      (node (ref "INT1") (pin "23") (pinfunction "23_23") (pintype "passive"))
      (node (ref "P9") (pin "23") (pinfunction "23_23") (pintype "bidirectional"))
    )
    (net (code "18") (name "/DY_RST") (class "Default")
      (node (ref "INT1") (pin "9") (pinfunction "9_9") (pintype "passive"))
      (node (ref "P8") (pin "22") (pinfunction "22_22") (pintype "bidirectional"))
    )
    (net (code "19") (name "/DY_RX") (class "Default")
      (node (ref "IC7") (pin "8") (pinfunction "RIN2_8") (pintype "bidirectional"))
      (node (ref "R76") (pin "1") (pinfunction "1_1") (pintype "passive"))
    )
    (net (code "20") (name "/DY_TX") (class "Default")
      (node (ref "IC7") (pin "7") (pinfunction "DOUT2_7") (pintype "bidirectional"))
      (node (ref "R77") (pin "1") (pinfunction "1_1") (pintype "passive"))
    )
    (net (code "21") (name "/DY_ZERO") (class "Default")
      (node (ref "INT2") (pin "24") (pinfunction "24_24") (pintype "passive"))
      (node (ref "P8") (pin "37") (pinfunction "37_37") (pintype "bidirectional"))
    )
    (net (code "22") (name "/DZ_FMVT") (class "Default")
      (node (ref "INT2") (pin "12") (pinfunction "12_12") (pintype "passive"))
      (node (ref "P8") (pin "46") (pinfunction "46_46") (pintype "bidirectional"))
    )
    (net (code "23") (name "/DZ_GO") (class "Default")
      (node (ref "INT1") (pin "22") (pinfunction "22_22") (pintype "passive"))
      (node (ref "P9") (pin "14") (pinfunction "14_14") (pintype "bidirectional"))
    )
    (net (code "24") (name "/DZ_RST") (class "Default")
      (node (ref "INT1") (pin "11") (pinfunction "11_11") (pintype "passive"))
      (node (ref "P8") (pin "3") (pinfunction "3_3") (pintype "bidirectional"))
    )
    (net (code "25") (name "/DZ_RX") (class "Default")
      (node (ref "IC2") (pin "8") (pinfunction "RIN2_8") (pintype "bidirectional"))
      (node (ref "R69") (pin "1") (pinfunction "1_1") (pintype "passive"))
    )
    (net (code "26") (name "/DZ_TX") (class "Default")
      (node (ref "IC2") (pin "7") (pinfunction "DOUT2_7") (pintype "bidirectional"))
      (node (ref "R75") (pin "1") (pinfunction "1_1") (pintype "passive"))
    )
    (net (code "27") (name "/DZ_ZERO") (class "Default")
      (node (ref "INT2") (pin "21") (pinfunction "21_21") (pintype "passive"))
      (node (ref "P8") (pin "38") (pinfunction "38_38") (pintype "bidirectional"))
    )
    (net (code "28") (name "/GT_FMVT") (class "Default")
      (node (ref "INT2") (pin "6") (pinfunction "6_6") (pintype "passive"))
      (node (ref "P8") (pin "10") (pinfunction "10_10") (pintype "bidirectional"))
    )
    (net (code "29") (name "/GT_GO") (class "Default")
      (node (ref "INT1") (pin "38") (pinfunction "38_38") (pintype "passive"))
      (node (ref "P8") (pin "15") (pinfunction "15_15") (pintype "bidirectional"))
    )
    (net (code "30") (name "/GT_RST") (class "Default")
      (node (ref "INT1") (pin "5") (pinfunction "5_5") (pintype "passive"))
      (node (ref "P8") (pin "6") (pinfunction "6_6") (pintype "bidirectional"))
    )
    (net (code "31") (name "/GT_RX") (class "Default")
      (node (ref "IC10") (pin "13") (pinfunction "RIN1_13") (pintype "bidirectional"))
      (node (ref "R73") (pin "1") (pinfunction "1_1") (pintype "passive"))
    )
    (net (code "32") (name "/GT_TX") (class "Default")
      (node (ref "IC10") (pin "14") (pinfunction "DOUT1_14") (pintype "bidirectional"))
      (node (ref "R72") (pin "1") (pinfunction "1_1") (pintype "passive"))
    )
    (net (code "33") (name "/GT_ZERO") (class "Default")
      (node (ref "INT2") (pin "26") (pinfunction "26_26") (pintype "passive"))
      (node (ref "P8") (pin "39") (pinfunction "39_39") (pintype "bidirectional"))
    )
    (net (code "34") (name "/GX_FMVT") (class "Default")
      (node (ref "INT2") (pin "9") (pinfunction "9_9") (pintype "passive"))
      (node (ref "P8") (pin "18") (pinfunction "18_18") (pintype "bidirectional"))
    )
    (net (code "35") (name "/GX_GO") (class "Default")
      (node (ref "INT1") (pin "34") (pinfunction "34_34") (pintype "passive"))
      (node (ref "P8") (pin "12") (pinfunction "12_12") (pintype "bidirectional"))
    )
    (net (code "36") (name "/GX_RST") (class "Default")
      (node (ref "INT1") (pin "10") (pinfunction "10_10") (pintype "passive"))
      (node (ref "P8") (pin "25") (pinfunction "25_25") (pintype "bidirectional"))
    )
    (net (code "37") (name "/GX_RX") (class "Default")
      (node (ref "IC4") (pin "13") (pinfunction "RIN1_13") (pintype "bidirectional"))
      (node (ref "R45") (pin "1") (pinfunction "1_1") (pintype "passive"))
    )
    (net (code "38") (name "/GX_TX") (class "Default")
      (node (ref "IC4") (pin "14") (pinfunction "DOUT1_14") (pintype "bidirectional"))
      (node (ref "R44") (pin "1") (pinfunction "1_1") (pintype "passive"))
    )
    (net (code "39") (name "/GX_ZERO") (class "Default")
      (node (ref "INT2") (pin "27") (pinfunction "27_27") (pintype "passive"))
      (node (ref "P8") (pin "44") (pinfunction "44_44") (pintype "bidirectional"))
    )
    (net (code "40") (name "/GY_FMVT") (class "Default")
      (node (ref "INT2") (pin "7") (pinfunction "7_7") (pintype "passive"))
      (node (ref "P8") (pin "7") (pinfunction "7_7") (pintype "bidirectional"))
    )
    (net (code "41") (name "/GY_GO") (class "Default")
      (node (ref "INT1") (pin "35") (pinfunction "35_35") (pintype "passive"))
      (node (ref "P8") (pin "11") (pinfunction "11_11") (pintype "bidirectional"))
    )
    (net (code "42") (name "/GY_RST") (class "Default")
      (node (ref "INT1") (pin "8") (pinfunction "8_8") (pintype "passive"))
      (node (ref "P8") (pin "24") (pinfunction "24_24") (pintype "bidirectional"))
    )
    (net (code "43") (name "/GY_RX") (class "Default")
      (node (ref "IC7") (pin "13") (pinfunction "RIN1_13") (pintype "bidirectional"))
      (node (ref "R68") (pin "1") (pinfunction "1_1") (pintype "passive"))
    )
    (net (code "44") (name "/GY_TX") (class "Default")
      (node (ref "IC7") (pin "14") (pinfunction "DOUT1_14") (pintype "bidirectional"))
      (node (ref "R48") (pin "1") (pinfunction "1_1") (pintype "passive"))
    )
    (net (code "45") (name "/GY_ZERO") (class "Default")
      (node (ref "INT2") (pin "28") (pinfunction "28_28") (pintype "passive"))
      (node (ref "P8") (pin "41") (pinfunction "41_41") (pintype "bidirectional"))
    )
    (net (code "46") (name "/GZ_FMVT") (class "Default")
      (node (ref "INT2") (pin "5") (pinfunction "5_5") (pintype "passive"))
      (node (ref "P8") (pin "8") (pinfunction "8_8") (pintype "bidirectional"))
    )
    (net (code "47") (name "/GZ_GO") (class "Default")
      (node (ref "INT1") (pin "36") (pinfunction "36_36") (pintype "passive"))
      (node (ref "P8") (pin "16") (pinfunction "16_16") (pintype "bidirectional"))
    )
    (net (code "48") (name "/GZ_RST") (class "Default")
      (node (ref "INT1") (pin "6") (pinfunction "6_6") (pintype "passive"))
      (node (ref "P8") (pin "5") (pinfunction "5_5") (pintype "bidirectional"))
    )
    (net (code "49") (name "/GZ_RX") (class "Default")
      (node (ref "IC2") (pin "13") (pinfunction "RIN1_13") (pintype "bidirectional"))
      (node (ref "R71") (pin "1") (pinfunction "1_1") (pintype "passive"))
    )
    (net (code "50") (name "/GZ_TX") (class "Default")
      (node (ref "IC2") (pin "14") (pinfunction "DOUT1_14") (pintype "bidirectional"))
      (node (ref "R70") (pin "1") (pinfunction "1_1") (pintype "passive"))
    )
    (net (code "51") (name "/GZ_ZERO") (class "Default")
      (node (ref "INT2") (pin "25") (pinfunction "25_25") (pintype "passive"))
      (node (ref "P8") (pin "42") (pinfunction "42_42") (pintype "bidirectional"))
    )
    (net (code "52") (name "/INFO_AR_URG") (class "Default")
      (node (ref "INT2") (pin "16") (pinfunction "16_16") (pintype "passive"))
      (node (ref "P8") (pin "34") (pinfunction "34_34") (pintype "bidirectional"))
    )
    (net (code "53") (name "/IRQ_T_N") (class "Default")
      (node (ref "IC9") (pin "7") (pinfunction "~{IRQ}_7") (pintype "bidirectional"))
      (node (ref "P9") (pin "28") (pinfunction "28_28") (pintype "bidirectional"))
      (node (ref "R67") (pin "1") (pinfunction "1_1") (pintype "passive"))
    )
    (net (code "54") (name "/IRQ_X_N") (class "Default")
      (node (ref "IC3") (pin "7") (pinfunction "~{IRQ}_7") (pintype "bidirectional"))
      (node (ref "P9") (pin "31") (pinfunction "31_31") (pintype "bidirectional"))
      (node (ref "R64") (pin "1") (pinfunction "1_1") (pintype "passive"))
    )
    (net (code "55") (name "/IRQ_Y_N") (class "Default")
      (node (ref "IC6") (pin "7") (pinfunction "~{IRQ}_7") (pintype "bidirectional"))
      (node (ref "P9") (pin "29") (pinfunction "29_29") (pintype "bidirectional"))
      (node (ref "R32") (pin "1") (pinfunction "1_1") (pintype "passive"))
    )
    (net (code "56") (name "/IRQ_Z_N") (class "Default")
      (node (ref "IC1") (pin "7") (pinfunction "~{IRQ}_7") (pintype "bidirectional"))
      (node (ref "P9") (pin "30") (pinfunction "30_30") (pintype "bidirectional"))
      (node (ref "R19") (pin "1") (pinfunction "1_1") (pintype "passive"))
    )
    (net (code "57") (name "/ORD_AR_URG") (class "Default")
      (node (ref "INT1") (pin "15") (pinfunction "15_15") (pintype "passive"))
      (node (ref "P9") (pin "12") (pinfunction "12_12") (pintype "bidirectional"))
    )
    (net (code "58") (name "/PORTE_DB") (class "Default")
      (node (ref "INT2") (pin "19") (pinfunction "19_19") (pintype "passive"))
      (node (ref "P8") (pin "28") (pinfunction "28_28") (pintype "bidirectional"))
    )
    (net (code "59") (name "/PORTE_DH") (class "Default")
      (node (ref "INT2") (pin "20") (pinfunction "20_20") (pintype "passive"))
      (node (ref "P8") (pin "30") (pinfunction "30_30") (pintype "bidirectional"))
    )
    (net (code "60") (name "/PORTE_GB") (class "Default")
      (node (ref "INT2") (pin "17") (pinfunction "17_17") (pintype "passive"))
      (node (ref "P8") (pin "27") (pinfunction "27_27") (pintype "bidirectional"))
    )
    (net (code "61") (name "/PORTE_GH") (class "Default")
      (node (ref "INT2") (pin "18") (pinfunction "18_18") (pintype "passive"))
      (node (ref "P8") (pin "29") (pinfunction "29_29") (pintype "bidirectional"))
    )
    (net (code "62") (name "/R2") (class "Default")
      (node (ref "INT2") (pin "15") (pinfunction "15_15") (pintype "passive"))
      (node (ref "P8") (pin "20") (pinfunction "20_20") (pintype "bidirectional"))
    )
    (net (code "63") (name "/R3") (class "Default")
      (node (ref "INT1") (pin "14") (pinfunction "14_14") (pintype "passive"))
      (node (ref "P8") (pin "26") (pinfunction "26_26") (pintype "bidirectional"))
    )
    (net (code "64") (name "/RST_N") (class "Default")
      (node (ref "IC1") (pin "1") (pinfunction "~{RST}_1") (pintype "bidirectional"))
      (node (ref "IC3") (pin "1") (pinfunction "~{RST}_1") (pintype "bidirectional"))
      (node (ref "IC6") (pin "1") (pinfunction "~{RST}_1") (pintype "bidirectional"))
      (node (ref "IC9") (pin "1") (pinfunction "~{RST}_1") (pintype "bidirectional"))
      (node (ref "P9") (pin "27") (pinfunction "27_27") (pintype "bidirectional"))
      (node (ref "R11") (pin "1") (pinfunction "1_1") (pintype "passive"))
    )
    (net (code "65") (name "/SCL") (class "Default")
      (node (ref "IC1") (pin "3") (pinfunction "SCLK/SCL_3") (pintype "bidirectional"))
      (node (ref "IC3") (pin "3") (pinfunction "SCLK/SCL_3") (pintype "bidirectional"))
      (node (ref "IC6") (pin "3") (pinfunction "SCLK/SCL_3") (pintype "bidirectional"))
      (node (ref "IC9") (pin "3") (pinfunction "SCLK/SCL_3") (pintype "bidirectional"))
      (node (ref "P9") (pin "19") (pinfunction "19_19") (pintype "bidirectional"))
      (node (ref "R59") (pin "2") (pinfunction "2_2") (pintype "passive"))
    )
    (net (code "66") (name "/SDA") (class "Default")
      (node (ref "IC1") (pin "2") (pinfunction "MISO/SDA_2") (pintype "bidirectional"))
      (node (ref "IC3") (pin "2") (pinfunction "MISO/SDA_2") (pintype "bidirectional"))
      (node (ref "IC6") (pin "2") (pinfunction "MISO/SDA_2") (pintype "bidirectional"))
      (node (ref "IC9") (pin "2") (pinfunction "MISO/SDA_2") (pintype "bidirectional"))
      (node (ref "P9") (pin "20") (pinfunction "20_20") (pintype "bidirectional"))
      (node (ref "R12") (pin "2") (pinfunction "2_2") (pintype "passive"))
    )
    (net (code "67") (name "GND") (class "Default")
      (node (ref "C12") (pin "1") (pinfunction "1_1") (pintype "passive"))
      (node (ref "C13") (pin "2") (pinfunction "2_2") (pintype "passive"))
      (node (ref "C14") (pin "2") (pinfunction "2_2") (pintype "passive"))
      (node (ref "C15") (pin "2") (pinfunction "2_2") (pintype "passive"))
      (node (ref "C16") (pin "1") (pinfunction "1_1") (pintype "passive"))
      (node (ref "C17") (pin "1") (pinfunction "1_1") (pintype "passive"))
      (node (ref "C18") (pin "2") (pinfunction "2_2") (pintype "passive"))
      (node (ref "C19") (pin "1") (pinfunction "1_1") (pintype "passive"))
      (node (ref "C22") (pin "1") (pinfunction "1_1") (pintype "passive"))
      (node (ref "C23") (pin "2") (pinfunction "2_2") (pintype "passive"))
      (node (ref "C24") (pin "2") (pinfunction "2_2") (pintype "passive"))
      (node (ref "C25") (pin "2") (pinfunction "2_2") (pintype "passive"))
      (node (ref "C26") (pin "1") (pinfunction "1_1") (pintype "passive"))
      (node (ref "C27") (pin "1") (pinfunction "1_1") (pintype "passive"))
      (node (ref "C28") (pin "2") (pinfunction "2_2") (pintype "passive"))
      (node (ref "C29") (pin "1") (pinfunction "1_1") (pintype "passive"))
      (node (ref "C3") (pin "1") (pinfunction "1_1") (pintype "passive"))
      (node (ref "C32") (pin "1") (pinfunction "1_1") (pintype "passive"))
      (node (ref "C33") (pin "2") (pinfunction "2_2") (pintype "passive"))
      (node (ref "C34") (pin "2") (pinfunction "2_2") (pintype "passive"))
      (node (ref "C35") (pin "2") (pinfunction "2_2") (pintype "passive"))
      (node (ref "C36") (pin "1") (pinfunction "1_1") (pintype "passive"))
      (node (ref "C37") (pin "-") (pinfunction "-_-") (pintype "passive"))
      (node (ref "C38") (pin "1") (pinfunction "1_1") (pintype "passive"))
      (node (ref "C39") (pin "1") (pinfunction "1_1") (pintype "passive"))
      (node (ref "C4") (pin "2") (pinfunction "2_2") (pintype "passive"))
      (node (ref "C40") (pin "2") (pinfunction "2_2") (pintype "passive"))
      (node (ref "C41") (pin "1") (pinfunction "1_1") (pintype "passive"))
      (node (ref "C42") (pin "-") (pinfunction "-_-") (pintype "passive"))
      (node (ref "C43") (pin "2") (pinfunction "2_2") (pintype "passive"))
      (node (ref "C44") (pin "2") (pinfunction "2_2") (pintype "passive"))
      (node (ref "C45") (pin "-") (pinfunction "-_-") (pintype "passive"))
      (node (ref "C5") (pin "2") (pinfunction "2_2") (pintype "passive"))
      (node (ref "C6") (pin "2") (pinfunction "2_2") (pintype "passive"))
      (node (ref "C7") (pin "1") (pinfunction "1_1") (pintype "passive"))
      (node (ref "C8") (pin "1") (pinfunction "1_1") (pintype "passive"))
      (node (ref "C9") (pin "2") (pinfunction "2_2") (pintype "passive"))
      (node (ref "IC1") (pin "10") (pinfunction "DGND_10") (pintype "bidirectional"))
      (node (ref "IC1") (pin "29") (pinfunction "AGND_29") (pintype "bidirectional"))
      (node (ref "IC1") (pin "33") (pinfunction "THERMAL_PAD_33") (pintype "bidirectional"))
      (node (ref "IC1") (pin "9") (pinfunction "SPI/~{I2C}_9") (pintype "bidirectional"))
      (node (ref "IC10") (pin "15") (pinfunction "GND_15") (pintype "bidirectional"))
      (node (ref "IC12") (pin "7") (pinfunction "GND_7") (pintype "bidirectional"))
      (node (ref "IC13") (pin "7") (pinfunction "GND_7") (pintype "bidirectional"))
      (node (ref "IC2") (pin "15") (pinfunction "GND_15") (pintype "bidirectional"))
      (node (ref "IC3") (pin "10") (pinfunction "DGND_10") (pintype "bidirectional"))
      (node (ref "IC3") (pin "29") (pinfunction "AGND_29") (pintype "bidirectional"))
      (node (ref "IC3") (pin "33") (pinfunction "THERMAL_PAD_33") (pintype "bidirectional"))
      (node (ref "IC3") (pin "9") (pinfunction "SPI/~{I2C}_9") (pintype "bidirectional"))
      (node (ref "IC4") (pin "15") (pinfunction "GND_15") (pintype "bidirectional"))
      (node (ref "IC5") (pin "7") (pinfunction "GND_7") (pintype "bidirectional"))
      (node (ref "IC6") (pin "10") (pinfunction "DGND_10") (pintype "bidirectional"))
      (node (ref "IC6") (pin "29") (pinfunction "AGND_29") (pintype "bidirectional"))
      (node (ref "IC6") (pin "33") (pinfunction "THERMAL_PAD_33") (pintype "bidirectional"))
      (node (ref "IC6") (pin "9") (pinfunction "SPI/~{I2C}_9") (pintype "bidirectional"))
      (node (ref "IC7") (pin "15") (pinfunction "GND_15") (pintype "bidirectional"))
      (node (ref "IC8") (pin "7") (pinfunction "GND_7") (pintype "bidirectional"))
      (node (ref "IC9") (pin "10") (pinfunction "DGND_10") (pintype "bidirectional"))
      (node (ref "IC9") (pin "29") (pinfunction "AGND_29") (pintype "bidirectional"))
      (node (ref "IC9") (pin "33") (pinfunction "THERMAL_PAD_33") (pintype "bidirectional"))
      (node (ref "IC9") (pin "9") (pinfunction "SPI/~{I2C}_9") (pintype "bidirectional"))
      (node (ref "INT1") (pin "40") (pinfunction "40_40") (pintype "passive"))
      (node (ref "INT2") (pin "40") (pinfunction "40_40") (pintype "passive"))
      (node (ref "LED1") (pin "K") (pinfunction "C_K") (pintype "passive"))
      (node (ref "LED2") (pin "K") (pinfunction "C_K") (pintype "passive"))
      (node (ref "LED_DX1") (pin "1") (pinfunction "1_1") (pintype "passive"))
      (node (ref "LED_DX1") (pin "3") (pinfunction "3_3") (pintype "passive"))
      (node (ref "LED_DX2") (pin "1") (pinfunction "1_1") (pintype "passive"))
      (node (ref "LED_DX2") (pin "3") (pinfunction "3_3") (pintype "passive"))
      (node (ref "LED_DX3") (pin "1") (pinfunction "1_1") (pintype "passive"))
      (node (ref "LED_DX3") (pin "3") (pinfunction "3_3") (pintype "passive"))
      (node (ref "LED_DX4") (pin "1") (pinfunction "1_1") (pintype "passive"))
      (node (ref "LED_DX4") (pin "3") (pinfunction "3_3") (pintype "passive"))
      (node (ref "LED_GX1") (pin "1") (pinfunction "1_1") (pintype "passive"))
      (node (ref "LED_GX1") (pin "3") (pinfunction "3_3") (pintype "passive"))
      (node (ref "LED_GX2") (pin "1") (pinfunction "1_1") (pintype "passive"))
      (node (ref "LED_GX2") (pin "3") (pinfunction "3_3") (pintype "passive"))
      (node (ref "LED_GX3") (pin "1") (pinfunction "1_1") (pintype "passive"))
      (node (ref "LED_GX3") (pin "3") (pinfunction "3_3") (pintype "passive"))
      (node (ref "LED_GX4") (pin "1") (pinfunction "1_1") (pintype "passive"))
      (node (ref "LED_GX4") (pin "3") (pinfunction "3_3") (pintype "passive"))
      (node (ref "P8") (pin "1") (pinfunction "1_1") (pintype "bidirectional"))
      (node (ref "P8") (pin "2") (pinfunction "2_2") (pintype "bidirectional"))
      (node (ref "P9") (pin "1") (pinfunction "1_1") (pintype "bidirectional"))
      (node (ref "P9") (pin "2") (pinfunction "2_2") (pintype "bidirectional"))
      (node (ref "P9") (pin "43") (pinfunction "43_43") (pintype "bidirectional"))
      (node (ref "P9") (pin "44") (pinfunction "44_44") (pintype "bidirectional"))
      (node (ref "P9") (pin "45") (pinfunction "45_45") (pintype "bidirectional"))
      (node (ref "P9") (pin "46") (pinfunction "46_46") (pintype "bidirectional"))
      (node (ref "Q1") (pin "3") (pinfunction "S_3") (pintype "passive"))
      (node (ref "R10") (pin "2") (pinfunction "2_2") (pintype "passive"))
      (node (ref "R28") (pin "2") (pinfunction "2_2") (pintype "passive"))
      (node (ref "R29") (pin "2") (pinfunction "2_2") (pintype "passive"))
      (node (ref "R41") (pin "1") (pinfunction "1_1") (pintype "passive"))
      (node (ref "R56") (pin "2") (pinfunction "2_2") (pintype "passive"))
      (node (ref "R57") (pin "2") (pinfunction "2_2") (pintype "passive"))
      (node (ref "R61") (pin "2") (pinfunction "2_2") (pintype "passive"))
      (node (ref "R62") (pin "2") (pinfunction "2_2") (pintype "passive"))
      (node (ref "R9") (pin "2") (pinfunction "2_2") (pintype "passive"))
      (node (ref "X1") (pin "1") (pinfunction "1_1") (pintype "passive"))
      (node (ref "X1") (pin "G1") (pinfunction "G1_G1") (pintype "passive"))
      (node (ref "X1") (pin "G2") (pinfunction "G2_G2") (pintype "passive"))
      (node (ref "X2") (pin "1") (pinfunction "1_1") (pintype "passive"))
      (node (ref "X2") (pin "G1") (pinfunction "G1_G1") (pintype "passive"))
      (node (ref "X2") (pin "G2") (pinfunction "G2_G2") (pintype "passive"))
      (node (ref "X3") (pin "1") (pinfunction "1_1") (pintype "passive"))
      (node (ref "X3") (pin "G1") (pinfunction "G1_G1") (pintype "passive"))
      (node (ref "X3") (pin "G2") (pinfunction "G2_G2") (pintype "passive"))
      (node (ref "X4") (pin "1") (pinfunction "1_1") (pintype "passive"))
      (node (ref "X4") (pin "G1") (pinfunction "G1_G1") (pintype "passive"))
      (node (ref "X4") (pin "G2") (pinfunction "G2_G2") (pintype "passive"))
      (node (ref "X5") (pin "1") (pinfunction "1_1") (pintype "passive"))
      (node (ref "X5") (pin "G1") (pinfunction "G1_G1") (pintype "passive"))
      (node (ref "X5") (pin "G2") (pinfunction "G2_G2") (pintype "passive"))
      (node (ref "X6") (pin "1") (pinfunction "1_1") (pintype "passive"))
      (node (ref "X6") (pin "G1") (pinfunction "G1_G1") (pintype "passive"))
      (node (ref "X6") (pin "G2") (pinfunction "G2_G2") (pintype "passive"))
      (node (ref "X7") (pin "1") (pinfunction "1_1") (pintype "passive"))
      (node (ref "X7") (pin "G1") (pinfunction "G1_G1") (pintype "passive"))
      (node (ref "X7") (pin "G2") (pinfunction "G2_G2") (pintype "passive"))
      (node (ref "X8") (pin "1") (pinfunction "1_1") (pintype "passive"))
      (node (ref "X8") (pin "G1") (pinfunction "G1_G1") (pintype "passive"))
      (node (ref "X8") (pin "G2") (pinfunction "G2_G2") (pintype "passive"))
    )
    (net (code "68") (name "Net-(IC1-RX0)") (class "Default")
      (node (ref "IC1") (pin "19") (pinfunction "RX0_19") (pintype "bidirectional"))
      (node (ref "IC2") (pin "12") (pinfunction "ROUT1_12") (pintype "bidirectional"))
      (node (ref "IC5") (pin "9") (pinfunction "4A_9") (pintype "input"))
      (node (ref "R4") (pin "1") (pinfunction "1_1") (pintype "passive"))
    )
    (net (code "69") (name "Net-(IC1-RX1)") (class "Default")
      (node (ref "IC1") (pin "20") (pinfunction "RX1_20") (pintype "bidirectional"))
      (node (ref "IC2") (pin "9") (pinfunction "ROUT2_9") (pintype "bidirectional"))
      (node (ref "IC5") (pin "5") (pinfunction "3A_5") (pintype "input"))
      (node (ref "R3") (pin "1") (pinfunction "1_1") (pintype "passive"))
    )
    (net (code "70") (name "Net-(IC1-TX0)") (class "Default")
      (node (ref "IC1") (pin "18") (pinfunction "TX0_18") (pintype "bidirectional"))
      (node (ref "IC2") (pin "11") (pinfunction "DIN1_11") (pintype "bidirectional"))
      (node (ref "IC5") (pin "11") (pinfunction "5A_11") (pintype "input"))
      (node (ref "R1") (pin "2") (pinfunction "2_2") (pintype "passive"))
    )
    (net (code "71") (name "Net-(IC1-TX1)") (class "Default")
      (node (ref "IC1") (pin "17") (pinfunction "TX1_17") (pintype "bidirectional"))
      (node (ref "IC2") (pin "10") (pinfunction "DIN2_10") (pintype "bidirectional"))
      (node (ref "IC5") (pin "13") (pinfunction "6A_13") (pintype "input"))
      (node (ref "R2") (pin "2") (pinfunction "2_2") (pintype "passive"))
    )
    (net (code "72") (name "Net-(IC1-V18)") (class "Default")
      (node (ref "C9") (pin "1") (pinfunction "1_1") (pintype "passive"))
      (node (ref "IC1") (pin "31") (pinfunction "V18_31") (pintype "bidirectional"))
    )
    (net (code "73") (name "Net-(IC1-XIN)") (class "Default")
      (node (ref "IC1") (pin "26") (pinfunction "XIN_26") (pintype "bidirectional"))
      (node (ref "XTAL1") (pin "1") (pinfunction "1_1") (pintype "passive"))
    )
    (net (code "74") (name "Net-(IC1-XOUT)") (class "Default")
      (node (ref "IC1") (pin "27") (pinfunction "XOUT_27") (pintype "bidirectional"))
      (node (ref "XTAL1") (pin "2") (pinfunction "2_2") (pintype "passive"))
    )
    (net (code "75") (name "Net-(IC2-C1+)") (class "Default")
      (node (ref "C1") (pin "2") (pinfunction "2_2") (pintype "passive"))
      (node (ref "IC2") (pin "1") (pinfunction "C1+_1") (pintype "bidirectional"))
    )
    (net (code "76") (name "Net-(IC2-C1-)") (class "Default")
      (node (ref "C1") (pin "1") (pinfunction "1_1") (pintype "passive"))
      (node (ref "IC2") (pin "3") (pinfunction "C1-_3") (pintype "bidirectional"))
    )
    (net (code "77") (name "Net-(IC2-C2+)") (class "Default")
      (node (ref "C2") (pin "2") (pinfunction "2_2") (pintype "passive"))
      (node (ref "IC2") (pin "4") (pinfunction "C2+_4") (pintype "bidirectional"))
    )
    (net (code "78") (name "Net-(IC2-C2-)") (class "Default")
      (node (ref "C2") (pin "1") (pinfunction "1_1") (pintype "passive"))
      (node (ref "IC2") (pin "5") (pinfunction "C2-_5") (pintype "bidirectional"))
    )
    (net (code "79") (name "Net-(IC2-V+)") (class "Default")
      (node (ref "C3") (pin "2") (pinfunction "2_2") (pintype "passive"))
      (node (ref "IC2") (pin "2") (pinfunction "V+_2") (pintype "bidirectional"))
    )
    (net (code "80") (name "Net-(IC2-V-)") (class "Default")
      (node (ref "C4") (pin "1") (pinfunction "1_1") (pintype "passive"))
      (node (ref "IC2") (pin "6") (pinfunction "V-_6") (pintype "bidirectional"))
    )
    (net (code "81") (name "Net-(IC3-V18)") (class "Default")
      (node (ref "C18") (pin "1") (pinfunction "1_1") (pintype "passive"))
      (node (ref "IC3") (pin "31") (pinfunction "V18_31") (pintype "bidirectional"))
    )
    (net (code "82") (name "Net-(IC3-XIN)") (class "Default")
      (node (ref "IC3") (pin "26") (pinfunction "XIN_26") (pintype "bidirectional"))
      (node (ref "XTAL2") (pin "1") (pinfunction "1_1") (pintype "passive"))
    )
    (net (code "83") (name "Net-(IC3-XOUT)") (class "Default")
      (node (ref "IC3") (pin "27") (pinfunction "XOUT_27") (pintype "bidirectional"))
      (node (ref "XTAL2") (pin "2") (pinfunction "2_2") (pintype "passive"))
    )
    (net (code "84") (name "Net-(IC4-C1+)") (class "Default")
      (node (ref "C10") (pin "2") (pinfunction "2_2") (pintype "passive"))
      (node (ref "IC4") (pin "1") (pinfunction "C1+_1") (pintype "bidirectional"))
    )
    (net (code "85") (name "Net-(IC4-C1-)") (class "Default")
      (node (ref "C10") (pin "1") (pinfunction "1_1") (pintype "passive"))
      (node (ref "IC4") (pin "3") (pinfunction "C1-_3") (pintype "bidirectional"))
    )
    (net (code "86") (name "Net-(IC4-C2+)") (class "Default")
      (node (ref "C11") (pin "2") (pinfunction "2_2") (pintype "passive"))
      (node (ref "IC4") (pin "4") (pinfunction "C2+_4") (pintype "bidirectional"))
    )
    (net (code "87") (name "Net-(IC4-C2-)") (class "Default")
      (node (ref "C11") (pin "1") (pinfunction "1_1") (pintype "passive"))
      (node (ref "IC4") (pin "5") (pinfunction "C2-_5") (pintype "bidirectional"))
    )
    (net (code "88") (name "Net-(IC4-V+)") (class "Default")
      (node (ref "C12") (pin "2") (pinfunction "2_2") (pintype "passive"))
      (node (ref "IC4") (pin "2") (pinfunction "V+_2") (pintype "bidirectional"))
    )
    (net (code "89") (name "Net-(IC4-V-)") (class "Default")
      (node (ref "C13") (pin "1") (pinfunction "1_1") (pintype "passive"))
      (node (ref "IC4") (pin "6") (pinfunction "V-_6") (pintype "bidirectional"))
    )
    (net (code "90") (name "Net-(IC5-1A)") (class "Default")
      (node (ref "IC5") (pin "1") (pinfunction "1A_1") (pintype "input"))
      (node (ref "R18") (pin "2") (pinfunction "2_2") (pintype "passive"))
    )
    (net (code "91") (name "Net-(IC5-1Y)") (class "Default")
      (node (ref "IC5") (pin "2") (pinfunction "1Y_2") (pintype "output"))
      (node (ref "R6") (pin "1") (pinfunction "1_1") (pintype "passive"))
    )
    (net (code "92") (name "Net-(IC5-2A)") (class "Default")
      (node (ref "IC5") (pin "3") (pinfunction "2A_3") (pintype "input"))
      (node (ref "R17") (pin "2") (pinfunction "2_2") (pintype "passive"))
    )
    (net (code "93") (name "Net-(IC5-2Y)") (class "Default")
      (node (ref "IC5") (pin "4") (pinfunction "2Y_4") (pintype "output"))
      (node (ref "R5") (pin "1") (pinfunction "1_1") (pintype "passive"))
    )
    (net (code "94") (name "Net-(IC5-3Y)") (class "Default")
      (node (ref "IC5") (pin "6") (pinfunction "3Y_6") (pintype "output"))
      (node (ref "R7") (pin "1") (pinfunction "1_1") (pintype "passive"))
    )
    (net (code "95") (name "Net-(IC5-4Y)") (class "Default")
      (node (ref "IC5") (pin "8") (pinfunction "4Y_8") (pintype "output"))
      (node (ref "R8") (pin "1") (pinfunction "1_1") (pintype "passive"))
    )
    (net (code "96") (name "Net-(IC5-5Y)") (class "Default")
      (node (ref "IC5") (pin "10") (pinfunction "5Y_10") (pintype "output"))
      (node (ref "R9") (pin "1") (pinfunction "1_1") (pintype "passive"))
    )
    (net (code "97") (name "Net-(IC5-6Y)") (class "Default")
      (node (ref "IC5") (pin "12") (pinfunction "6Y_12") (pintype "output"))
      (node (ref "R10") (pin "1") (pinfunction "1_1") (pintype "passive"))
    )
    (net (code "98") (name "Net-(IC6-RX0)") (class "Default")
      (node (ref "IC6") (pin "19") (pinfunction "RX0_19") (pintype "bidirectional"))
      (node (ref "IC7") (pin "12") (pinfunction "ROUT1_12") (pintype "bidirectional"))
      (node (ref "IC8") (pin "9") (pinfunction "4A_9") (pintype "input"))
      (node (ref "R23") (pin "1") (pinfunction "1_1") (pintype "passive"))
    )
    (net (code "99") (name "Net-(IC6-RX1)") (class "Default")
      (node (ref "IC6") (pin "20") (pinfunction "RX1_20") (pintype "bidirectional"))
      (node (ref "IC7") (pin "9") (pinfunction "ROUT2_9") (pintype "bidirectional"))
      (node (ref "IC8") (pin "5") (pinfunction "3A_5") (pintype "input"))
      (node (ref "R22") (pin "1") (pinfunction "1_1") (pintype "passive"))
    )
    (net (code "100") (name "Net-(IC6-TX0)") (class "Default")
      (node (ref "IC6") (pin "18") (pinfunction "TX0_18") (pintype "bidirectional"))
      (node (ref "IC7") (pin "11") (pinfunction "DIN1_11") (pintype "bidirectional"))
      (node (ref "IC8") (pin "11") (pinfunction "5A_11") (pintype "input"))
      (node (ref "R20") (pin "2") (pinfunction "2_2") (pintype "passive"))
    )
    (net (code "101") (name "Net-(IC6-TX1)") (class "Default")
      (node (ref "IC6") (pin "17") (pinfunction "TX1_17") (pintype "bidirectional"))
      (node (ref "IC7") (pin "10") (pinfunction "DIN2_10") (pintype "bidirectional"))
      (node (ref "IC8") (pin "13") (pinfunction "6A_13") (pintype "input"))
      (node (ref "R21") (pin "2") (pinfunction "2_2") (pintype "passive"))
    )
    (net (code "102") (name "Net-(IC6-V18)") (class "Default")
      (node (ref "C28") (pin "1") (pinfunction "1_1") (pintype "passive"))
      (node (ref "IC6") (pin "31") (pinfunction "V18_31") (pintype "bidirectional"))
    )
    (net (code "103") (name "Net-(IC6-XIN)") (class "Default")
      (node (ref "IC6") (pin "26") (pinfunction "XIN_26") (pintype "bidirectional"))
      (node (ref "XTAL3") (pin "1") (pinfunction "1_1") (pintype "passive"))
    )
    (net (code "104") (name "Net-(IC6-XOUT)") (class "Default")
      (node (ref "IC6") (pin "27") (pinfunction "XOUT_27") (pintype "bidirectional"))
      (node (ref "XTAL3") (pin "2") (pinfunction "2_2") (pintype "passive"))
    )
    (net (code "105") (name "Net-(IC7-C1+)") (class "Default")
      (node (ref "C20") (pin "2") (pinfunction "2_2") (pintype "passive"))
      (node (ref "IC7") (pin "1") (pinfunction "C1+_1") (pintype "bidirectional"))
    )
    (net (code "106") (name "Net-(IC7-C1-)") (class "Default")
      (node (ref "C20") (pin "1") (pinfunction "1_1") (pintype "passive"))
      (node (ref "IC7") (pin "3") (pinfunction "C1-_3") (pintype "bidirectional"))
    )
    (net (code "107") (name "Net-(IC7-C2+)") (class "Default")
      (node (ref "C21") (pin "2") (pinfunction "2_2") (pintype "passive"))
      (node (ref "IC7") (pin "4") (pinfunction "C2+_4") (pintype "bidirectional"))
    )
    (net (code "108") (name "Net-(IC7-C2-)") (class "Default")
      (node (ref "C21") (pin "1") (pinfunction "1_1") (pintype "passive"))
      (node (ref "IC7") (pin "5") (pinfunction "C2-_5") (pintype "bidirectional"))
    )
    (net (code "109") (name "Net-(IC7-V+)") (class "Default")
      (node (ref "C22") (pin "2") (pinfunction "2_2") (pintype "passive"))
      (node (ref "IC7") (pin "2") (pinfunction "V+_2") (pintype "bidirectional"))
    )
    (net (code "110") (name "Net-(IC7-V-)") (class "Default")
      (node (ref "C23") (pin "1") (pinfunction "1_1") (pintype "passive"))
      (node (ref "IC7") (pin "6") (pinfunction "V-_6") (pintype "bidirectional"))
    )
    (net (code "111") (name "Net-(IC8-1A)") (class "Default")
      (node (ref "IC8") (pin "1") (pinfunction "1A_1") (pintype "input"))
      (node (ref "R31") (pin "2") (pinfunction "2_2") (pintype "passive"))
    )
    (net (code "112") (name "Net-(IC8-1Y)") (class "Default")
      (node (ref "IC8") (pin "2") (pinfunction "1Y_2") (pintype "output"))
      (node (ref "R25") (pin "1") (pinfunction "1_1") (pintype "passive"))
    )
    (net (code "113") (name "Net-(IC8-2A)") (class "Default")
      (node (ref "IC8") (pin "3") (pinfunction "2A_3") (pintype "input"))
      (node (ref "R30") (pin "2") (pinfunction "2_2") (pintype "passive"))
    )
    (net (code "114") (name "Net-(IC8-2Y)") (class "Default")
      (node (ref "IC8") (pin "4") (pinfunction "2Y_4") (pintype "output"))
      (node (ref "R24") (pin "1") (pinfunction "1_1") (pintype "passive"))
    )
    (net (code "115") (name "Net-(IC8-3Y)") (class "Default")
      (node (ref "IC8") (pin "6") (pinfunction "3Y_6") (pintype "output"))
      (node (ref "R26") (pin "1") (pinfunction "1_1") (pintype "passive"))
    )
    (net (code "116") (name "Net-(IC8-4Y)") (class "Default")
      (node (ref "IC8") (pin "8") (pinfunction "4Y_8") (pintype "output"))
      (node (ref "R27") (pin "1") (pinfunction "1_1") (pintype "passive"))
    )
    (net (code "117") (name "Net-(IC8-5Y)") (class "Default")
      (node (ref "IC8") (pin "10") (pinfunction "5Y_10") (pintype "output"))
      (node (ref "R28") (pin "1") (pinfunction "1_1") (pintype "passive"))
    )
    (net (code "118") (name "Net-(IC8-6Y)") (class "Default")
      (node (ref "IC8") (pin "12") (pinfunction "6Y_12") (pintype "output"))
      (node (ref "R29") (pin "1") (pinfunction "1_1") (pintype "passive"))
    )
    (net (code "119") (name "Net-(IC9-V18)") (class "Default")
      (node (ref "C40") (pin "1") (pinfunction "1_1") (pintype "passive"))
      (node (ref "IC9") (pin "31") (pinfunction "V18_31") (pintype "bidirectional"))
    )
    (net (code "120") (name "Net-(IC9-XIN)") (class "Default")
      (node (ref "IC9") (pin "26") (pinfunction "XIN_26") (pintype "bidirectional"))
      (node (ref "XTAL4") (pin "1") (pinfunction "1_1") (pintype "passive"))
    )
    (net (code "121") (name "Net-(IC9-XOUT)") (class "Default")
      (node (ref "IC9") (pin "27") (pinfunction "XOUT_27") (pintype "bidirectional"))
      (node (ref "XTAL4") (pin "2") (pinfunction "2_2") (pintype "passive"))
    )
    (net (code "122") (name "Net-(IC10-C1+)") (class "Default")
      (node (ref "C30") (pin "2") (pinfunction "2_2") (pintype "passive"))
      (node (ref "IC10") (pin "1") (pinfunction "C1+_1") (pintype "bidirectional"))
    )
    (net (code "123") (name "Net-(IC10-C1-)") (class "Default")
      (node (ref "C30") (pin "1") (pinfunction "1_1") (pintype "passive"))
      (node (ref "IC10") (pin "3") (pinfunction "C1-_3") (pintype "bidirectional"))
    )
    (net (code "124") (name "Net-(IC10-C2+)") (class "Default")
      (node (ref "C31") (pin "2") (pinfunction "2_2") (pintype "passive"))
      (node (ref "IC10") (pin "4") (pinfunction "C2+_4") (pintype "bidirectional"))
    )
    (net (code "125") (name "Net-(IC10-C2-)") (class "Default")
      (node (ref "C31") (pin "1") (pinfunction "1_1") (pintype "passive"))
      (node (ref "IC10") (pin "5") (pinfunction "C2-_5") (pintype "bidirectional"))
    )
    (net (code "126") (name "Net-(IC10-DIN1)") (class "Default")
      (node (ref "IC10") (pin "11") (pinfunction "DIN1_11") (pintype "bidirectional"))
      (node (ref "IC12") (pin "11") (pinfunction "5A_11") (pintype "input"))
      (node (ref "IC9") (pin "18") (pinfunction "TX0_18") (pintype "bidirectional"))
      (node (ref "R33") (pin "2") (pinfunction "2_2") (pintype "passive"))
    )
    (net (code "127") (name "Net-(IC10-DIN2)") (class "Default")
      (node (ref "IC10") (pin "10") (pinfunction "DIN2_10") (pintype "bidirectional"))
      (node (ref "IC12") (pin "13") (pinfunction "6A_13") (pintype "input"))
      (node (ref "IC9") (pin "17") (pinfunction "TX1_17") (pintype "bidirectional"))
      (node (ref "R35") (pin "2") (pinfunction "2_2") (pintype "passive"))
    )
    (net (code "128") (name "Net-(IC10-ROUT1)") (class "Default")
      (node (ref "IC10") (pin "12") (pinfunction "ROUT1_12") (pintype "bidirectional"))
      (node (ref "IC12") (pin "9") (pinfunction "4A_9") (pintype "input"))
      (node (ref "IC9") (pin "19") (pinfunction "RX0_19") (pintype "bidirectional"))
      (node (ref "R49") (pin "1") (pinfunction "1_1") (pintype "passive"))
    )
    (net (code "129") (name "Net-(IC10-ROUT2)") (class "Default")
      (node (ref "IC10") (pin "9") (pinfunction "ROUT2_9") (pintype "bidirectional"))
      (node (ref "IC12") (pin "5") (pinfunction "3A_5") (pintype "input"))
      (node (ref "IC9") (pin "20") (pinfunction "RX1_20") (pintype "bidirectional"))
      (node (ref "R36") (pin "1") (pinfunction "1_1") (pintype "passive"))
    )
    (net (code "130") (name "Net-(IC10-V+)") (class "Default")
      (node (ref "C32") (pin "2") (pinfunction "2_2") (pintype "passive"))
      (node (ref "IC10") (pin "2") (pinfunction "V+_2") (pintype "bidirectional"))
    )
    (net (code "131") (name "Net-(IC10-V-)") (class "Default")
      (node (ref "C33") (pin "1") (pinfunction "1_1") (pintype "passive"))
      (node (ref "IC10") (pin "6") (pinfunction "V-_6") (pintype "bidirectional"))
    )
    (net (code "132") (name "Net-(IC11-GND)") (class "Default")
      (node (ref "IC11") (pin "2") (pinfunction "GND_2") (pintype "passive"))
      (node (ref "R40") (pin "1") (pinfunction "1_1") (pintype "passive"))
      (node (ref "R41") (pin "2") (pinfunction "2_2") (pintype "passive"))
    )
    (net (code "133") (name "Net-(IC11-VI)") (class "Default")
      (node (ref "C43") (pin "1") (pinfunction "1_1") (pintype "passive"))
      (node (ref "IC11") (pin "1") (pinfunction "VI_1") (pintype "input"))
      (node (ref "Q2") (pin "D") (pinfunction "D_D") (pintype "passive"))
    )
    (net (code "134") (name "Net-(IC12-1A)") (class "Default")
      (node (ref "IC12") (pin "1") (pinfunction "1A_1") (pintype "input"))
      (node (ref "R66") (pin "2") (pinfunction "2_2") (pintype "passive"))
    )
    (net (code "135") (name "Net-(IC12-1Y)") (class "Default")
      (node (ref "IC12") (pin "2") (pinfunction "1Y_2") (pintype "output"))
      (node (ref "R51") (pin "1") (pinfunction "1_1") (pintype "passive"))
    )
    (net (code "136") (name "Net-(IC12-2A)") (class "Default")
      (node (ref "IC12") (pin "3") (pinfunction "2A_3") (pintype "input"))
      (node (ref "R65") (pin "2") (pinfunction "2_2") (pintype "passive"))
    )
    (net (code "137") (name "Net-(IC12-2Y)") (class "Default")
      (node (ref "IC12") (pin "4") (pinfunction "2Y_4") (pintype "output"))
      (node (ref "R50") (pin "1") (pinfunction "1_1") (pintype "passive"))
    )
    (net (code "138") (name "Net-(IC12-3Y)") (class "Default")
      (node (ref "IC12") (pin "6") (pinfunction "3Y_6") (pintype "output"))
      (node (ref "R52") (pin "1") (pinfunction "1_1") (pintype "passive"))
    )
    (net (code "139") (name "Net-(IC12-4Y)") (class "Default")
      (node (ref "IC12") (pin "8") (pinfunction "4Y_8") (pintype "output"))
      (node (ref "R60") (pin "1") (pinfunction "1_1") (pintype "passive"))
    )
    (net (code "140") (name "Net-(IC12-5Y)") (class "Default")
      (node (ref "IC12") (pin "10") (pinfunction "5Y_10") (pintype "output"))
      (node (ref "R61") (pin "1") (pinfunction "1_1") (pintype "passive"))
    )
    (net (code "141") (name "Net-(IC12-6Y)") (class "Default")
      (node (ref "IC12") (pin "12") (pinfunction "6Y_12") (pintype "output"))
      (node (ref "R62") (pin "1") (pinfunction "1_1") (pintype "passive"))
    )
    (net (code "142") (name "Net-(IC13-1A)") (class "Default")
      (node (ref "IC13") (pin "1") (pinfunction "1A_1") (pintype "input"))
      (node (ref "R63") (pin "2") (pinfunction "2_2") (pintype "passive"))
    )
    (net (code "143") (name "Net-(IC13-1Y)") (class "Default")
      (node (ref "IC13") (pin "2") (pinfunction "1Y_2") (pintype "output"))
      (node (ref "R53") (pin "1") (pinfunction "1_1") (pintype "passive"))
    )
    (net (code "144") (name "Net-(IC13-2A)") (class "Default")
      (node (ref "IC13") (pin "3") (pinfunction "2A_3") (pintype "input"))
      (node (ref "R58") (pin "2") (pinfunction "2_2") (pintype "passive"))
    )
    (net (code "145") (name "Net-(IC13-2Y)") (class "Default")
      (node (ref "IC13") (pin "4") (pinfunction "2Y_4") (pintype "output"))
      (node (ref "R34") (pin "1") (pinfunction "1_1") (pintype "passive"))
    )
    (net (code "146") (name "Net-(IC13-3A)") (class "Default")
      (node (ref "IC13") (pin "5") (pinfunction "3A_5") (pintype "input"))
      (node (ref "IC3") (pin "20") (pinfunction "RX1_20") (pintype "bidirectional"))
      (node (ref "IC4") (pin "9") (pinfunction "ROUT2_9") (pintype "bidirectional"))
      (node (ref "R15") (pin "1") (pinfunction "1_1") (pintype "passive"))
    )
    (net (code "147") (name "Net-(IC13-3Y)") (class "Default")
      (node (ref "IC13") (pin "6") (pinfunction "3Y_6") (pintype "output"))
      (node (ref "R54") (pin "1") (pinfunction "1_1") (pintype "passive"))
    )
    (net (code "148") (name "Net-(IC13-4A)") (class "Default")
      (node (ref "IC13") (pin "9") (pinfunction "4A_9") (pintype "input"))
      (node (ref "IC3") (pin "19") (pinfunction "RX0_19") (pintype "bidirectional"))
      (node (ref "IC4") (pin "12") (pinfunction "ROUT1_12") (pintype "bidirectional"))
      (node (ref "R16") (pin "1") (pinfunction "1_1") (pintype "passive"))
    )
    (net (code "149") (name "Net-(IC13-4Y)") (class "Default")
      (node (ref "IC13") (pin "8") (pinfunction "4Y_8") (pintype "output"))
      (node (ref "R55") (pin "1") (pinfunction "1_1") (pintype "passive"))
    )
    (net (code "150") (name "Net-(IC13-5A)") (class "Default")
      (node (ref "IC13") (pin "11") (pinfunction "5A_11") (pintype "input"))
      (node (ref "IC3") (pin "18") (pinfunction "TX0_18") (pintype "bidirectional"))
      (node (ref "IC4") (pin "11") (pinfunction "DIN1_11") (pintype "bidirectional"))
      (node (ref "R13") (pin "2") (pinfunction "2_2") (pintype "passive"))
    )
    (net (code "151") (name "Net-(IC13-5Y)") (class "Default")
      (node (ref "IC13") (pin "10") (pinfunction "5Y_10") (pintype "output"))
      (node (ref "R56") (pin "1") (pinfunction "1_1") (pintype "passive"))
    )
    (net (code "152") (name "Net-(IC13-6A)") (class "Default")
      (node (ref "IC13") (pin "13") (pinfunction "6A_13") (pintype "input"))
      (node (ref "IC3") (pin "17") (pinfunction "TX1_17") (pintype "bidirectional"))
      (node (ref "IC4") (pin "10") (pinfunction "DIN2_10") (pintype "bidirectional"))
      (node (ref "R14") (pin "2") (pinfunction "2_2") (pintype "passive"))
    )
    (net (code "153") (name "Net-(IC13-6Y)") (class "Default")
      (node (ref "IC13") (pin "12") (pinfunction "6Y_12") (pintype "output"))
      (node (ref "R57") (pin "1") (pinfunction "1_1") (pintype "passive"))
    )
    (net (code "154") (name "Net-(LED1-PadA)") (class "Default")
      (node (ref "LED1") (pin "A") (pinfunction "A_A") (pintype "passive"))
      (node (ref "R38") (pin "1") (pinfunction "1_1") (pintype "passive"))
    )
    (net (code "155") (name "Net-(LED2-PadA)") (class "Default")
      (node (ref "LED2") (pin "A") (pinfunction "A_A") (pintype "passive"))
      (node (ref "R42") (pin "1") (pinfunction "1_1") (pintype "passive"))
    )
    (net (code "156") (name "Net-(LED_DX1-Pad2)") (class "Default")
      (node (ref "LED_DX1") (pin "2") (pinfunction "2_2") (pintype "passive"))
      (node (ref "R55") (pin "2") (pinfunction "2_2") (pintype "passive"))
    )
    (net (code "157") (name "Net-(LED_DX1-Pad4)") (class "Default")
      (node (ref "LED_DX1") (pin "4") (pinfunction "4_4") (pintype "passive"))
      (node (ref "R54") (pin "2") (pinfunction "2_2") (pintype "passive"))
    )
    (net (code "158") (name "Net-(LED_DX2-Pad2)") (class "Default")
      (node (ref "LED_DX2") (pin "2") (pinfunction "2_2") (pintype "passive"))
      (node (ref "R8") (pin "2") (pinfunction "2_2") (pintype "passive"))
    )
    (net (code "159") (name "Net-(LED_DX2-Pad4)") (class "Default")
      (node (ref "LED_DX2") (pin "4") (pinfunction "4_4") (pintype "passive"))
      (node (ref "R7") (pin "2") (pinfunction "2_2") (pintype "passive"))
    )
    (net (code "160") (name "Net-(LED_DX3-Pad2)") (class "Default")
      (node (ref "LED_DX3") (pin "2") (pinfunction "2_2") (pintype "passive"))
      (node (ref "R27") (pin "2") (pinfunction "2_2") (pintype "passive"))
    )
    (net (code "161") (name "Net-(LED_DX3-Pad4)") (class "Default")
      (node (ref "LED_DX3") (pin "4") (pinfunction "4_4") (pintype "passive"))
      (node (ref "R26") (pin "2") (pinfunction "2_2") (pintype "passive"))
    )
    (net (code "162") (name "Net-(LED_DX4-Pad2)") (class "Default")
      (node (ref "LED_DX4") (pin "2") (pinfunction "2_2") (pintype "passive"))
      (node (ref "R60") (pin "2") (pinfunction "2_2") (pintype "passive"))
    )
    (net (code "163") (name "Net-(LED_DX4-Pad4)") (class "Default")
      (node (ref "LED_DX4") (pin "4") (pinfunction "4_4") (pintype "passive"))
      (node (ref "R52") (pin "2") (pinfunction "2_2") (pintype "passive"))
    )
    (net (code "164") (name "Net-(LED_GX1-Pad2)") (class "Default")
      (node (ref "LED_GX1") (pin "2") (pinfunction "2_2") (pintype "passive"))
      (node (ref "R34") (pin "2") (pinfunction "2_2") (pintype "passive"))
    )
    (net (code "165") (name "Net-(LED_GX1-Pad4)") (class "Default")
      (node (ref "LED_GX1") (pin "4") (pinfunction "4_4") (pintype "passive"))
      (node (ref "R53") (pin "2") (pinfunction "2_2") (pintype "passive"))
    )
    (net (code "166") (name "Net-(LED_GX2-Pad2)") (class "Default")
      (node (ref "LED_GX2") (pin "2") (pinfunction "2_2") (pintype "passive"))
      (node (ref "R5") (pin "2") (pinfunction "2_2") (pintype "passive"))
    )
    (net (code "167") (name "Net-(LED_GX2-Pad4)") (class "Default")
      (node (ref "LED_GX2") (pin "4") (pinfunction "4_4") (pintype "passive"))
      (node (ref "R6") (pin "2") (pinfunction "2_2") (pintype "passive"))
    )
    (net (code "168") (name "Net-(LED_GX3-Pad2)") (class "Default")
      (node (ref "LED_GX3") (pin "2") (pinfunction "2_2") (pintype "passive"))
      (node (ref "R24") (pin "2") (pinfunction "2_2") (pintype "passive"))
    )
    (net (code "169") (name "Net-(LED_GX3-Pad4)") (class "Default")
      (node (ref "LED_GX3") (pin "4") (pinfunction "4_4") (pintype "passive"))
      (node (ref "R25") (pin "2") (pinfunction "2_2") (pintype "passive"))
    )
    (net (code "170") (name "Net-(LED_GX4-Pad2)") (class "Default")
      (node (ref "LED_GX4") (pin "2") (pinfunction "2_2") (pintype "passive"))
      (node (ref "R50") (pin "2") (pinfunction "2_2") (pintype "passive"))
    )
    (net (code "171") (name "Net-(LED_GX4-Pad4)") (class "Default")
      (node (ref "LED_GX4") (pin "4") (pinfunction "4_4") (pintype "passive"))
      (node (ref "R51") (pin "2") (pinfunction "2_2") (pintype "passive"))
    )
    (net (code "172") (name "Net-(Q1-D)") (class "Default")
      (node (ref "Q1") (pin "1") (pinfunction "D_1") (pintype "passive"))
      (node (ref "Q2") (pin "G") (pinfunction "G_G") (pintype "passive"))
      (node (ref "R39") (pin "2") (pinfunction "2_2") (pintype "passive"))
    )
    (net (code "173") (name "Net-(Q1-G)") (class "Default")
      (node (ref "C42") (pin "+") (pinfunction "+_+") (pintype "passive"))
      (node (ref "Q1") (pin "2") (pinfunction "G_2") (pintype "passive"))
      (node (ref "R37") (pin "2") (pinfunction "2_2") (pintype "passive"))
    )
    (net (code "174") (name "Net-(R43-Pad2)") (class "Default")
      (node (ref "R43") (pin "2") (pinfunction "2_2") (pintype "passive"))
      (node (ref "X8") (pin "4") (pinfunction "4_4") (pintype "passive"))
    )
    (net (code "175") (name "Net-(R44-Pad2)") (class "Default")
      (node (ref "R44") (pin "2") (pinfunction "2_2") (pintype "passive"))
      (node (ref "X1") (pin "3") (pinfunction "3_3") (pintype "passive"))
    )
    (net (code "176") (name "Net-(R45-Pad2)") (class "Default")
      (node (ref "R45") (pin "2") (pinfunction "2_2") (pintype "passive"))
      (node (ref "X1") (pin "4") (pinfunction "4_4") (pintype "passive"))
    )
    (net (code "177") (name "Net-(R46-Pad2)") (class "Default")
      (node (ref "R46") (pin "2") (pinfunction "2_2") (pintype "passive"))
      (node (ref "X5") (pin "3") (pinfunction "3_3") (pintype "passive"))
    )
    (net (code "178") (name "Net-(R47-Pad2)") (class "Default")
      (node (ref "R47") (pin "2") (pinfunction "2_2") (pintype "passive"))
      (node (ref "X5") (pin "4") (pinfunction "4_4") (pintype "passive"))
    )
    (net (code "179") (name "Net-(R48-Pad2)") (class "Default")
      (node (ref "R48") (pin "2") (pinfunction "2_2") (pintype "passive"))
      (node (ref "X2") (pin "3") (pinfunction "3_3") (pintype "passive"))
    )
    (net (code "180") (name "Net-(R68-Pad2)") (class "Default")
      (node (ref "R68") (pin "2") (pinfunction "2_2") (pintype "passive"))
      (node (ref "X2") (pin "4") (pinfunction "4_4") (pintype "passive"))
    )
    (net (code "181") (name "Net-(R69-Pad2)") (class "Default")
      (node (ref "R69") (pin "2") (pinfunction "2_2") (pintype "passive"))
      (node (ref "X7") (pin "4") (pinfunction "4_4") (pintype "passive"))
    )
    (net (code "182") (name "Net-(R70-Pad2)") (class "Default")
      (node (ref "R70") (pin "2") (pinfunction "2_2") (pintype "passive"))
      (node (ref "X3") (pin "3") (pinfunction "3_3") (pintype "passive"))
    )
    (net (code "183") (name "Net-(R71-Pad2)") (class "Default")
      (node (ref "R71") (pin "2") (pinfunction "2_2") (pintype "passive"))
      (node (ref "X3") (pin "4") (pinfunction "4_4") (pintype "passive"))
    )
    (net (code "184") (name "Net-(R72-Pad2)") (class "Default")
      (node (ref "R72") (pin "2") (pinfunction "2_2") (pintype "passive"))
      (node (ref "X4") (pin "3") (pinfunction "3_3") (pintype "passive"))
    )
    (net (code "185") (name "Net-(R73-Pad2)") (class "Default")
      (node (ref "R73") (pin "2") (pinfunction "2_2") (pintype "passive"))
      (node (ref "X4") (pin "4") (pinfunction "4_4") (pintype "passive"))
    )
    (net (code "186") (name "Net-(R74-Pad2)") (class "Default")
      (node (ref "R74") (pin "2") (pinfunction "2_2") (pintype "passive"))
      (node (ref "X8") (pin "3") (pinfunction "3_3") (pintype "passive"))
    )
    (net (code "187") (name "Net-(R75-Pad2)") (class "Default")
      (node (ref "R75") (pin "2") (pinfunction "2_2") (pintype "passive"))
      (node (ref "X7") (pin "3") (pinfunction "3_3") (pintype "passive"))
    )
    (net (code "188") (name "Net-(R76-Pad2)") (class "Default")
      (node (ref "R76") (pin "2") (pinfunction "2_2") (pintype "passive"))
      (node (ref "X6") (pin "4") (pinfunction "4_4") (pintype "passive"))
    )
    (net (code "189") (name "Net-(R77-Pad2)") (class "Default")
      (node (ref "R77") (pin "2") (pinfunction "2_2") (pintype "passive"))
      (node (ref "X6") (pin "3") (pinfunction "3_3") (pintype "passive"))
    )
    (net (code "190") (name "unconnected-(IC1-GPIO0-Pad11)") (class "Default")
      (node (ref "IC1") (pin "11") (pinfunction "GPIO0_11") (pintype "bidirectional"))
    )
    (net (code "191") (name "unconnected-(IC1-GPIO1-Pad13)") (class "Default")
      (node (ref "IC1") (pin "13") (pinfunction "GPIO1_13") (pintype "bidirectional"))
    )
    (net (code "192") (name "unconnected-(IC1-GPIO2-Pad23)") (class "Default")
      (node (ref "IC1") (pin "23") (pinfunction "GPIO2_23") (pintype "bidirectional"))
    )
    (net (code "193") (name "unconnected-(IC1-GPIO3-Pad24)") (class "Default")
      (node (ref "IC1") (pin "24") (pinfunction "GPIO3_24") (pintype "bidirectional"))
    )
    (net (code "194") (name "unconnected-(IC1-GPIO4-Pad12)") (class "Default")
      (node (ref "IC1") (pin "12") (pinfunction "GPIO4_12") (pintype "bidirectional"))
    )
    (net (code "195") (name "unconnected-(IC1-GPIO5-Pad14)") (class "Default")
      (node (ref "IC1") (pin "14") (pinfunction "GPIO5_14") (pintype "bidirectional"))
    )
    (net (code "196") (name "unconnected-(IC1-GPIO6-Pad28)") (class "Default")
      (node (ref "IC1") (pin "28") (pinfunction "GPIO6_28") (pintype "bidirectional"))
    )
    (net (code "197") (name "unconnected-(IC1-GPIO7-Pad4)") (class "Default")
      (node (ref "IC1") (pin "4") (pinfunction "GPIO7_4") (pintype "bidirectional"))
    )
    (net (code "198") (name "unconnected-(IC1-MOSI{slash}A1-Pad6)") (class "Default")
      (node (ref "IC1") (pin "6") (pinfunction "MOSI/A1_6") (pintype "bidirectional"))
    )
    (net (code "199") (name "unconnected-(IC1-~{CS}{slash}A0-Pad5)") (class "Default")
      (node (ref "IC1") (pin "5") (pinfunction "~{CS}/A0_5") (pintype "bidirectional"))
    )
    (net (code "200") (name "unconnected-(IC1-~{CTS0}-Pad15)") (class "Default")
      (node (ref "IC1") (pin "15") (pinfunction "~{CTS0}_15") (pintype "bidirectional"))
    )
    (net (code "201") (name "unconnected-(IC1-~{CTS1}-Pad16)") (class "Default")
      (node (ref "IC1") (pin "16") (pinfunction "~{CTS1}_16") (pintype "bidirectional"))
    )
    (net (code "202") (name "unconnected-(IC1-~{RTS0}-Pad21)") (class "Default")
      (node (ref "IC1") (pin "21") (pinfunction "~{RTS0}_21") (pintype "bidirectional"))
    )
    (net (code "203") (name "unconnected-(IC1-~{RTS1}-Pad22)") (class "Default")
      (node (ref "IC1") (pin "22") (pinfunction "~{RTS1}_22") (pintype "bidirectional"))
    )
    (net (code "204") (name "unconnected-(IC3-GPIO0-Pad11)") (class "Default")
      (node (ref "IC3") (pin "11") (pinfunction "GPIO0_11") (pintype "bidirectional"))
    )
    (net (code "205") (name "unconnected-(IC3-GPIO1-Pad13)") (class "Default")
      (node (ref "IC3") (pin "13") (pinfunction "GPIO1_13") (pintype "bidirectional"))
    )
    (net (code "206") (name "unconnected-(IC3-GPIO2-Pad23)") (class "Default")
      (node (ref "IC3") (pin "23") (pinfunction "GPIO2_23") (pintype "bidirectional"))
    )
    (net (code "207") (name "unconnected-(IC3-GPIO3-Pad24)") (class "Default")
      (node (ref "IC3") (pin "24") (pinfunction "GPIO3_24") (pintype "bidirectional"))
    )
    (net (code "208") (name "unconnected-(IC3-GPIO4-Pad12)") (class "Default")
      (node (ref "IC3") (pin "12") (pinfunction "GPIO4_12") (pintype "bidirectional"))
    )
    (net (code "209") (name "unconnected-(IC3-GPIO5-Pad14)") (class "Default")
      (node (ref "IC3") (pin "14") (pinfunction "GPIO5_14") (pintype "bidirectional"))
    )
    (net (code "210") (name "unconnected-(IC3-GPIO6-Pad28)") (class "Default")
      (node (ref "IC3") (pin "28") (pinfunction "GPIO6_28") (pintype "bidirectional"))
    )
    (net (code "211") (name "unconnected-(IC3-GPIO7-Pad4)") (class "Default")
      (node (ref "IC3") (pin "4") (pinfunction "GPIO7_4") (pintype "bidirectional"))
    )
    (net (code "212") (name "unconnected-(IC3-MOSI{slash}A1-Pad6)") (class "Default")
      (node (ref "IC3") (pin "6") (pinfunction "MOSI/A1_6") (pintype "bidirectional"))
    )
    (net (code "213") (name "unconnected-(IC3-~{CS}{slash}A0-Pad5)") (class "Default")
      (node (ref "IC3") (pin "5") (pinfunction "~{CS}/A0_5") (pintype "bidirectional"))
    )
    (net (code "214") (name "unconnected-(IC3-~{CTS0}-Pad15)") (class "Default")
      (node (ref "IC3") (pin "15") (pinfunction "~{CTS0}_15") (pintype "bidirectional"))
    )
    (net (code "215") (name "unconnected-(IC3-~{CTS1}-Pad16)") (class "Default")
      (node (ref "IC3") (pin "16") (pinfunction "~{CTS1}_16") (pintype "bidirectional"))
    )
    (net (code "216") (name "unconnected-(IC3-~{RTS0}-Pad21)") (class "Default")
      (node (ref "IC3") (pin "21") (pinfunction "~{RTS0}_21") (pintype "bidirectional"))
    )
    (net (code "217") (name "unconnected-(IC3-~{RTS1}-Pad22)") (class "Default")
      (node (ref "IC3") (pin "22") (pinfunction "~{RTS1}_22") (pintype "bidirectional"))
    )
    (net (code "218") (name "unconnected-(IC6-GPIO0-Pad11)") (class "Default")
      (node (ref "IC6") (pin "11") (pinfunction "GPIO0_11") (pintype "bidirectional"))
    )
    (net (code "219") (name "unconnected-(IC6-GPIO1-Pad13)") (class "Default")
      (node (ref "IC6") (pin "13") (pinfunction "GPIO1_13") (pintype "bidirectional"))
    )
    (net (code "220") (name "unconnected-(IC6-GPIO2-Pad23)") (class "Default")
      (node (ref "IC6") (pin "23") (pinfunction "GPIO2_23") (pintype "bidirectional"))
    )
    (net (code "221") (name "unconnected-(IC6-GPIO3-Pad24)") (class "Default")
      (node (ref "IC6") (pin "24") (pinfunction "GPIO3_24") (pintype "bidirectional"))
    )
    (net (code "222") (name "unconnected-(IC6-GPIO4-Pad12)") (class "Default")
      (node (ref "IC6") (pin "12") (pinfunction "GPIO4_12") (pintype "bidirectional"))
    )
    (net (code "223") (name "unconnected-(IC6-GPIO5-Pad14)") (class "Default")
      (node (ref "IC6") (pin "14") (pinfunction "GPIO5_14") (pintype "bidirectional"))
    )
    (net (code "224") (name "unconnected-(IC6-GPIO6-Pad28)") (class "Default")
      (node (ref "IC6") (pin "28") (pinfunction "GPIO6_28") (pintype "bidirectional"))
    )
    (net (code "225") (name "unconnected-(IC6-GPIO7-Pad4)") (class "Default")
      (node (ref "IC6") (pin "4") (pinfunction "GPIO7_4") (pintype "bidirectional"))
    )
    (net (code "226") (name "unconnected-(IC6-MOSI{slash}A1-Pad6)") (class "Default")
      (node (ref "IC6") (pin "6") (pinfunction "MOSI/A1_6") (pintype "bidirectional"))
    )
    (net (code "227") (name "unconnected-(IC6-~{CS}{slash}A0-Pad5)") (class "Default")
      (node (ref "IC6") (pin "5") (pinfunction "~{CS}/A0_5") (pintype "bidirectional"))
    )
    (net (code "228") (name "unconnected-(IC6-~{CTS0}-Pad15)") (class "Default")
      (node (ref "IC6") (pin "15") (pinfunction "~{CTS0}_15") (pintype "bidirectional"))
    )
    (net (code "229") (name "unconnected-(IC6-~{CTS1}-Pad16)") (class "Default")
      (node (ref "IC6") (pin "16") (pinfunction "~{CTS1}_16") (pintype "bidirectional"))
    )
    (net (code "230") (name "unconnected-(IC6-~{RTS0}-Pad21)") (class "Default")
      (node (ref "IC6") (pin "21") (pinfunction "~{RTS0}_21") (pintype "bidirectional"))
    )
    (net (code "231") (name "unconnected-(IC6-~{RTS1}-Pad22)") (class "Default")
      (node (ref "IC6") (pin "22") (pinfunction "~{RTS1}_22") (pintype "bidirectional"))
    )
    (net (code "232") (name "unconnected-(IC9-GPIO0-Pad11)") (class "Default")
      (node (ref "IC9") (pin "11") (pinfunction "GPIO0_11") (pintype "bidirectional"))
    )
    (net (code "233") (name "unconnected-(IC9-GPIO1-Pad13)") (class "Default")
      (node (ref "IC9") (pin "13") (pinfunction "GPIO1_13") (pintype "bidirectional"))
    )
    (net (code "234") (name "unconnected-(IC9-GPIO2-Pad23)") (class "Default")
      (node (ref "IC9") (pin "23") (pinfunction "GPIO2_23") (pintype "bidirectional"))
    )
    (net (code "235") (name "unconnected-(IC9-GPIO3-Pad24)") (class "Default")
      (node (ref "IC9") (pin "24") (pinfunction "GPIO3_24") (pintype "bidirectional"))
    )
    (net (code "236") (name "unconnected-(IC9-GPIO4-Pad12)") (class "Default")
      (node (ref "IC9") (pin "12") (pinfunction "GPIO4_12") (pintype "bidirectional"))
    )
    (net (code "237") (name "unconnected-(IC9-GPIO5-Pad14)") (class "Default")
      (node (ref "IC9") (pin "14") (pinfunction "GPIO5_14") (pintype "bidirectional"))
    )
    (net (code "238") (name "unconnected-(IC9-GPIO6-Pad28)") (class "Default")
      (node (ref "IC9") (pin "28") (pinfunction "GPIO6_28") (pintype "bidirectional"))
    )
    (net (code "239") (name "unconnected-(IC9-GPIO7-Pad4)") (class "Default")
      (node (ref "IC9") (pin "4") (pinfunction "GPIO7_4") (pintype "bidirectional"))
    )
    (net (code "240") (name "unconnected-(IC9-MOSI{slash}A1-Pad6)") (class "Default")
      (node (ref "IC9") (pin "6") (pinfunction "MOSI/A1_6") (pintype "bidirectional"))
    )
    (net (code "241") (name "unconnected-(IC9-~{CS}{slash}A0-Pad5)") (class "Default")
      (node (ref "IC9") (pin "5") (pinfunction "~{CS}/A0_5") (pintype "bidirectional"))
    )
    (net (code "242") (name "unconnected-(IC9-~{CTS0}-Pad15)") (class "Default")
      (node (ref "IC9") (pin "15") (pinfunction "~{CTS0}_15") (pintype "bidirectional"))
    )
    (net (code "243") (name "unconnected-(IC9-~{CTS1}-Pad16)") (class "Default")
      (node (ref "IC9") (pin "16") (pinfunction "~{CTS1}_16") (pintype "bidirectional"))
    )
    (net (code "244") (name "unconnected-(IC9-~{RTS0}-Pad21)") (class "Default")
      (node (ref "IC9") (pin "21") (pinfunction "~{RTS0}_21") (pintype "bidirectional"))
    )
    (net (code "245") (name "unconnected-(IC9-~{RTS1}-Pad22)") (class "Default")
      (node (ref "IC9") (pin "22") (pinfunction "~{RTS1}_22") (pintype "bidirectional"))
    )
    (net (code "246") (name "unconnected-(INT1-Pad1)") (class "Default")
      (node (ref "INT1") (pin "1") (pinfunction "1_1") (pintype "passive"))
    )
    (net (code "247") (name "unconnected-(INT1-Pad2)") (class "Default")
      (node (ref "INT1") (pin "2") (pinfunction "2_2") (pintype "passive"))
    )
    (net (code "248") (name "unconnected-(INT1-Pad4)") (class "Default")
      (node (ref "INT1") (pin "4") (pinfunction "4_4") (pintype "passive"))
    )
    (net (code "249") (name "unconnected-(INT1-Pad12)") (class "Default")
      (node (ref "INT1") (pin "12") (pinfunction "12_12") (pintype "passive"))
    )
    (net (code "250") (name "unconnected-(INT1-Pad17)") (class "Default")
      (node (ref "INT1") (pin "17") (pinfunction "17_17") (pintype "passive"))
    )
    (net (code "251") (name "unconnected-(INT1-Pad18)") (class "Default")
      (node (ref "INT1") (pin "18") (pinfunction "18_18") (pintype "passive"))
    )
    (net (code "252") (name "unconnected-(INT1-Pad19)") (class "Default")
      (node (ref "INT1") (pin "19") (pinfunction "19_19") (pintype "passive"))
    )
    (net (code "253") (name "unconnected-(INT1-Pad20)") (class "Default")
      (node (ref "INT1") (pin "20") (pinfunction "20_20") (pintype "passive"))
    )
    (net (code "254") (name "unconnected-(INT1-Pad25)") (class "Default")
      (node (ref "INT1") (pin "25") (pinfunction "25_25") (pintype "passive"))
    )
    (net (code "255") (name "unconnected-(INT1-Pad26)") (class "Default")
      (node (ref "INT1") (pin "26") (pinfunction "26_26") (pintype "passive"))
    )
    (net (code "256") (name "unconnected-(INT1-Pad27)") (class "Default")
      (node (ref "INT1") (pin "27") (pinfunction "27_27") (pintype "passive"))
    )
    (net (code "257") (name "unconnected-(INT1-Pad28)") (class "Default")
      (node (ref "INT1") (pin "28") (pinfunction "28_28") (pintype "passive"))
    )
    (net (code "258") (name "unconnected-(INT1-Pad29)") (class "Default")
      (node (ref "INT1") (pin "29") (pinfunction "29_29") (pintype "passive"))
    )
    (net (code "259") (name "unconnected-(INT1-Pad30)") (class "Default")
      (node (ref "INT1") (pin "30") (pinfunction "30_30") (pintype "passive"))
    )
    (net (code "260") (name "unconnected-(INT1-Pad31)") (class "Default")
      (node (ref "INT1") (pin "31") (pinfunction "31_31") (pintype "passive"))
    )
    (net (code "261") (name "unconnected-(INT1-Pad32)") (class "Default")
      (node (ref "INT1") (pin "32") (pinfunction "32_32") (pintype "passive"))
    )
    (net (code "262") (name "unconnected-(INT1-Pad33)") (class "Default")
      (node (ref "INT1") (pin "33") (pinfunction "33_33") (pintype "passive"))
    )
    (net (code "263") (name "unconnected-(INT1-Pad37)") (class "Default")
      (node (ref "INT1") (pin "37") (pinfunction "37_37") (pintype "passive"))
    )
    (net (code "264") (name "unconnected-(INT1-Pad39)") (class "Default")
      (node (ref "INT1") (pin "39") (pinfunction "39_39") (pintype "passive"))
    )
    (net (code "265") (name "unconnected-(INT2-Pad1)") (class "Default")
      (node (ref "INT2") (pin "1") (pinfunction "1_1") (pintype "passive"))
    )
    (net (code "266") (name "unconnected-(INT2-Pad2)") (class "Default")
      (node (ref "INT2") (pin "2") (pinfunction "2_2") (pintype "passive"))
    )
    (net (code "267") (name "unconnected-(INT2-Pad4)") (class "Default")
      (node (ref "INT2") (pin "4") (pinfunction "4_4") (pintype "passive"))
    )
    (net (code "268") (name "unconnected-(INT2-Pad11)") (class "Default")
      (node (ref "INT2") (pin "11") (pinfunction "11_11") (pintype "passive"))
    )
    (net (code "269") (name "unconnected-(INT2-Pad13)") (class "Default")
      (node (ref "INT2") (pin "13") (pinfunction "13_13") (pintype "passive"))
    )
    (net (code "270") (name "unconnected-(INT2-Pad29)") (class "Default")
      (node (ref "INT2") (pin "29") (pinfunction "29_29") (pintype "passive"))
    )
    (net (code "271") (name "unconnected-(INT2-Pad30)") (class "Default")
      (node (ref "INT2") (pin "30") (pinfunction "30_30") (pintype "passive"))
    )
    (net (code "272") (name "unconnected-(INT2-Pad31)") (class "Default")
      (node (ref "INT2") (pin "31") (pinfunction "31_31") (pintype "passive"))
    )
    (net (code "273") (name "unconnected-(INT2-Pad32)") (class "Default")
      (node (ref "INT2") (pin "32") (pinfunction "32_32") (pintype "passive"))
    )
    (net (code "274") (name "unconnected-(INT2-Pad33)") (class "Default")
      (node (ref "INT2") (pin "33") (pinfunction "33_33") (pintype "passive"))
    )
    (net (code "275") (name "unconnected-(INT2-Pad34)") (class "Default")
      (node (ref "INT2") (pin "34") (pinfunction "34_34") (pintype "passive"))
    )
    (net (code "276") (name "unconnected-(INT2-Pad35)") (class "Default")
      (node (ref "INT2") (pin "35") (pinfunction "35_35") (pintype "passive"))
    )
    (net (code "277") (name "unconnected-(INT2-Pad36)") (class "Default")
      (node (ref "INT2") (pin "36") (pinfunction "36_36") (pintype "passive"))
    )
    (net (code "278") (name "unconnected-(INT2-Pad37)") (class "Default")
      (node (ref "INT2") (pin "37") (pinfunction "37_37") (pintype "passive"))
    )
    (net (code "279") (name "unconnected-(INT2-Pad38)") (class "Default")
      (node (ref "INT2") (pin "38") (pinfunction "38_38") (pintype "passive"))
    )
    (net (code "280") (name "unconnected-(INT2-Pad39)") (class "Default")
      (node (ref "INT2") (pin "39") (pinfunction "39_39") (pintype "passive"))
    )
    (net (code "281") (name "unconnected-(P8-Pad13)") (class "Default")
      (node (ref "P8") (pin "13") (pinfunction "13_13") (pintype "bidirectional"))
    )
    (net (code "282") (name "unconnected-(P8-Pad14)") (class "Default")
      (node (ref "P8") (pin "14") (pinfunction "14_14") (pintype "bidirectional"))
    )
    (net (code "283") (name "unconnected-(P8-Pad17)") (class "Default")
      (node (ref "P8") (pin "17") (pinfunction "17_17") (pintype "bidirectional"))
    )
    (net (code "284") (name "unconnected-(P8-Pad19)") (class "Default")
      (node (ref "P8") (pin "19") (pinfunction "19_19") (pintype "bidirectional"))
    )
    (net (code "285") (name "unconnected-(P8-Pad31)") (class "Default")
      (node (ref "P8") (pin "31") (pinfunction "31_31") (pintype "bidirectional"))
    )
    (net (code "286") (name "unconnected-(P8-Pad32)") (class "Default")
      (node (ref "P8") (pin "32") (pinfunction "32_32") (pintype "bidirectional"))
    )
    (net (code "287") (name "unconnected-(P8-Pad33)") (class "Default")
      (node (ref "P8") (pin "33") (pinfunction "33_33") (pintype "bidirectional"))
    )
    (net (code "288") (name "unconnected-(P8-Pad35)") (class "Default")
      (node (ref "P8") (pin "35") (pinfunction "35_35") (pintype "bidirectional"))
    )
    (net (code "289") (name "unconnected-(P9-Pad3)") (class "Default")
      (node (ref "P9") (pin "3") (pinfunction "3_3") (pintype "bidirectional"))
    )
    (net (code "290") (name "unconnected-(P9-Pad4)") (class "Default")
      (node (ref "P9") (pin "4") (pinfunction "4_4") (pintype "bidirectional"))
    )
    (net (code "291") (name "unconnected-(P9-Pad7)") (class "Default")
      (node (ref "P9") (pin "7") (pinfunction "7_7") (pintype "bidirectional"))
    )
    (net (code "292") (name "unconnected-(P9-Pad8)") (class "Default")
      (node (ref "P9") (pin "8") (pinfunction "8_8") (pintype "bidirectional"))
    )
    (net (code "293") (name "unconnected-(P9-Pad9)") (class "Default")
      (node (ref "P9") (pin "9") (pinfunction "9_9") (pintype "bidirectional"))
    )
    (net (code "294") (name "unconnected-(P9-Pad10)") (class "Default")
      (node (ref "P9") (pin "10") (pinfunction "10_10") (pintype "bidirectional"))
    )
    (net (code "295") (name "unconnected-(P9-Pad11)") (class "Default")
      (node (ref "P9") (pin "11") (pinfunction "11_11") (pintype "bidirectional"))
    )
    (net (code "296") (name "unconnected-(P9-Pad13)") (class "Default")
      (node (ref "P9") (pin "13") (pinfunction "13_13") (pintype "bidirectional"))
    )
    (net (code "297") (name "unconnected-(P9-Pad17)") (class "Default")
      (node (ref "P9") (pin "17") (pinfunction "17_17") (pintype "bidirectional"))
    )
    (net (code "298") (name "unconnected-(P9-Pad18)") (class "Default")
      (node (ref "P9") (pin "18") (pinfunction "18_18") (pintype "bidirectional"))
    )
    (net (code "299") (name "unconnected-(P9-Pad21)") (class "Default")
      (node (ref "P9") (pin "21") (pinfunction "21_21") (pintype "bidirectional"))
    )
    (net (code "300") (name "unconnected-(P9-Pad22)") (class "Default")
      (node (ref "P9") (pin "22") (pinfunction "22_22") (pintype "bidirectional"))
    )
    (net (code "301") (name "unconnected-(P9-Pad24)") (class "Default")
      (node (ref "P9") (pin "24") (pinfunction "24_24") (pintype "bidirectional"))
    )
    (net (code "302") (name "unconnected-(P9-Pad25)") (class "Default")
      (node (ref "P9") (pin "25") (pinfunction "25_25") (pintype "bidirectional"))
    )
    (net (code "303") (name "unconnected-(P9-Pad26)") (class "Default")
      (node (ref "P9") (pin "26") (pinfunction "26_26") (pintype "bidirectional"))
    )
    (net (code "304") (name "unconnected-(P9-Pad32)") (class "Default")
      (node (ref "P9") (pin "32") (pinfunction "32_32") (pintype "bidirectional"))
    )
    (net (code "305") (name "unconnected-(P9-Pad33)") (class "Default")
      (node (ref "P9") (pin "33") (pinfunction "33_33") (pintype "bidirectional"))
    )
    (net (code "306") (name "unconnected-(P9-Pad34)") (class "Default")
      (node (ref "P9") (pin "34") (pinfunction "34_34") (pintype "bidirectional"))
    )
    (net (code "307") (name "unconnected-(P9-Pad35)") (class "Default")
      (node (ref "P9") (pin "35") (pinfunction "35_35") (pintype "bidirectional"))
    )
    (net (code "308") (name "unconnected-(P9-Pad36)") (class "Default")
      (node (ref "P9") (pin "36") (pinfunction "36_36") (pintype "bidirectional"))
    )
    (net (code "309") (name "unconnected-(P9-Pad37)") (class "Default")
      (node (ref "P9") (pin "37") (pinfunction "37_37") (pintype "bidirectional"))
    )
    (net (code "310") (name "unconnected-(P9-Pad38)") (class "Default")
      (node (ref "P9") (pin "38") (pinfunction "38_38") (pintype "bidirectional"))
    )
    (net (code "311") (name "unconnected-(P9-Pad39)") (class "Default")
      (node (ref "P9") (pin "39") (pinfunction "39_39") (pintype "bidirectional"))
    )
    (net (code "312") (name "unconnected-(P9-Pad40)") (class "Default")
      (node (ref "P9") (pin "40") (pinfunction "40_40") (pintype "bidirectional"))
    )
    (net (code "313") (name "unconnected-(P9-Pad41)") (class "Default")
      (node (ref "P9") (pin "41") (pinfunction "41_41") (pintype "bidirectional"))
    )
    (net (code "314") (name "unconnected-(P9-Pad42)") (class "Default")
      (node (ref "P9") (pin "42") (pinfunction "42_42") (pintype "bidirectional"))
    )
    (net (code "315") (name "unconnected-(X1-Pad2)") (class "Default")
      (node (ref "X1") (pin "2") (pinfunction "2_2") (pintype "passive"))
    )
    (net (code "316") (name "unconnected-(X1-Pad5)") (class "Default")
      (node (ref "X1") (pin "5") (pinfunction "5_5") (pintype "passive"))
    )
    (net (code "317") (name "unconnected-(X1-Pad6)") (class "Default")
      (node (ref "X1") (pin "6") (pinfunction "6_6") (pintype "passive"))
    )
    (net (code "318") (name "unconnected-(X1-Pad7)") (class "Default")
      (node (ref "X1") (pin "7") (pinfunction "7_7") (pintype "passive"))
    )
    (net (code "319") (name "unconnected-(X1-Pad8)") (class "Default")
      (node (ref "X1") (pin "8") (pinfunction "8_8") (pintype "passive"))
    )
    (net (code "320") (name "unconnected-(X1-Pad9)") (class "Default")
      (node (ref "X1") (pin "9") (pinfunction "9_9") (pintype "passive"))
    )
    (net (code "321") (name "unconnected-(X2-Pad2)") (class "Default")
      (node (ref "X2") (pin "2") (pinfunction "2_2") (pintype "passive"))
    )
    (net (code "322") (name "unconnected-(X2-Pad5)") (class "Default")
      (node (ref "X2") (pin "5") (pinfunction "5_5") (pintype "passive"))
    )
    (net (code "323") (name "unconnected-(X2-Pad6)") (class "Default")
      (node (ref "X2") (pin "6") (pinfunction "6_6") (pintype "passive"))
    )
    (net (code "324") (name "unconnected-(X2-Pad7)") (class "Default")
      (node (ref "X2") (pin "7") (pinfunction "7_7") (pintype "passive"))
    )
    (net (code "325") (name "unconnected-(X2-Pad8)") (class "Default")
      (node (ref "X2") (pin "8") (pinfunction "8_8") (pintype "passive"))
    )
    (net (code "326") (name "unconnected-(X2-Pad9)") (class "Default")
      (node (ref "X2") (pin "9") (pinfunction "9_9") (pintype "passive"))
    )
    (net (code "327") (name "unconnected-(X3-Pad2)") (class "Default")
      (node (ref "X3") (pin "2") (pinfunction "2_2") (pintype "passive"))
    )
    (net (code "328") (name "unconnected-(X3-Pad5)") (class "Default")
      (node (ref "X3") (pin "5") (pinfunction "5_5") (pintype "passive"))
    )
    (net (code "329") (name "unconnected-(X3-Pad6)") (class "Default")
      (node (ref "X3") (pin "6") (pinfunction "6_6") (pintype "passive"))
    )
    (net (code "330") (name "unconnected-(X3-Pad7)") (class "Default")
      (node (ref "X3") (pin "7") (pinfunction "7_7") (pintype "passive"))
    )
    (net (code "331") (name "unconnected-(X3-Pad8)") (class "Default")
      (node (ref "X3") (pin "8") (pinfunction "8_8") (pintype "passive"))
    )
    (net (code "332") (name "unconnected-(X3-Pad9)") (class "Default")
      (node (ref "X3") (pin "9") (pinfunction "9_9") (pintype "passive"))
    )
    (net (code "333") (name "unconnected-(X4-Pad2)") (class "Default")
      (node (ref "X4") (pin "2") (pinfunction "2_2") (pintype "passive"))
    )
    (net (code "334") (name "unconnected-(X4-Pad5)") (class "Default")
      (node (ref "X4") (pin "5") (pinfunction "5_5") (pintype "passive"))
    )
    (net (code "335") (name "unconnected-(X4-Pad6)") (class "Default")
      (node (ref "X4") (pin "6") (pinfunction "6_6") (pintype "passive"))
    )
    (net (code "336") (name "unconnected-(X4-Pad7)") (class "Default")
      (node (ref "X4") (pin "7") (pinfunction "7_7") (pintype "passive"))
    )
    (net (code "337") (name "unconnected-(X4-Pad8)") (class "Default")
      (node (ref "X4") (pin "8") (pinfunction "8_8") (pintype "passive"))
    )
    (net (code "338") (name "unconnected-(X4-Pad9)") (class "Default")
      (node (ref "X4") (pin "9") (pinfunction "9_9") (pintype "passive"))
    )
    (net (code "339") (name "unconnected-(X5-Pad2)") (class "Default")
      (node (ref "X5") (pin "2") (pinfunction "2_2") (pintype "passive"))
    )
    (net (code "340") (name "unconnected-(X5-Pad5)") (class "Default")
      (node (ref "X5") (pin "5") (pinfunction "5_5") (pintype "passive"))
    )
    (net (code "341") (name "unconnected-(X5-Pad6)") (class "Default")
      (node (ref "X5") (pin "6") (pinfunction "6_6") (pintype "passive"))
    )
    (net (code "342") (name "unconnected-(X5-Pad7)") (class "Default")
      (node (ref "X5") (pin "7") (pinfunction "7_7") (pintype "passive"))
    )
    (net (code "343") (name "unconnected-(X5-Pad8)") (class "Default")
      (node (ref "X5") (pin "8") (pinfunction "8_8") (pintype "passive"))
    )
    (net (code "344") (name "unconnected-(X5-Pad9)") (class "Default")
      (node (ref "X5") (pin "9") (pinfunction "9_9") (pintype "passive"))
    )
    (net (code "345") (name "unconnected-(X6-Pad2)") (class "Default")
      (node (ref "X6") (pin "2") (pinfunction "2_2") (pintype "passive"))
    )
    (net (code "346") (name "unconnected-(X6-Pad5)") (class "Default")
      (node (ref "X6") (pin "5") (pinfunction "5_5") (pintype "passive"))
    )
    (net (code "347") (name "unconnected-(X6-Pad6)") (class "Default")
      (node (ref "X6") (pin "6") (pinfunction "6_6") (pintype "passive"))
    )
    (net (code "348") (name "unconnected-(X6-Pad7)") (class "Default")
      (node (ref "X6") (pin "7") (pinfunction "7_7") (pintype "passive"))
    )
    (net (code "349") (name "unconnected-(X6-Pad8)") (class "Default")
      (node (ref "X6") (pin "8") (pinfunction "8_8") (pintype "passive"))
    )
    (net (code "350") (name "unconnected-(X6-Pad9)") (class "Default")
      (node (ref "X6") (pin "9") (pinfunction "9_9") (pintype "passive"))
    )
    (net (code "351") (name "unconnected-(X7-Pad2)") (class "Default")
      (node (ref "X7") (pin "2") (pinfunction "2_2") (pintype "passive"))
    )
    (net (code "352") (name "unconnected-(X7-Pad5)") (class "Default")
      (node (ref "X7") (pin "5") (pinfunction "5_5") (pintype "passive"))
    )
    (net (code "353") (name "unconnected-(X7-Pad6)") (class "Default")
      (node (ref "X7") (pin "6") (pinfunction "6_6") (pintype "passive"))
    )
    (net (code "354") (name "unconnected-(X7-Pad7)") (class "Default")
      (node (ref "X7") (pin "7") (pinfunction "7_7") (pintype "passive"))
    )
    (net (code "355") (name "unconnected-(X7-Pad8)") (class "Default")
      (node (ref "X7") (pin "8") (pinfunction "8_8") (pintype "passive"))
    )
    (net (code "356") (name "unconnected-(X7-Pad9)") (class "Default")
      (node (ref "X7") (pin "9") (pinfunction "9_9") (pintype "passive"))
    )
    (net (code "357") (name "unconnected-(X8-Pad2)") (class "Default")
      (node (ref "X8") (pin "2") (pinfunction "2_2") (pintype "passive"))
    )
    (net (code "358") (name "unconnected-(X8-Pad5)") (class "Default")
      (node (ref "X8") (pin "5") (pinfunction "5_5") (pintype "passive"))
    )
    (net (code "359") (name "unconnected-(X8-Pad6)") (class "Default")
      (node (ref "X8") (pin "6") (pinfunction "6_6") (pintype "passive"))
    )
    (net (code "360") (name "unconnected-(X8-Pad7)") (class "Default")
      (node (ref "X8") (pin "7") (pinfunction "7_7") (pintype "passive"))
    )
    (net (code "361") (name "unconnected-(X8-Pad8)") (class "Default")
      (node (ref "X8") (pin "8") (pinfunction "8_8") (pintype "passive"))
    )
    (net (code "362") (name "unconnected-(X8-Pad9)") (class "Default")
      (node (ref "X8") (pin "9") (pinfunction "9_9") (pintype "passive"))
    )
  )
)
